# CN-Cape006-via08.net
KiCad netlist of a schematic drawn in EAGLE
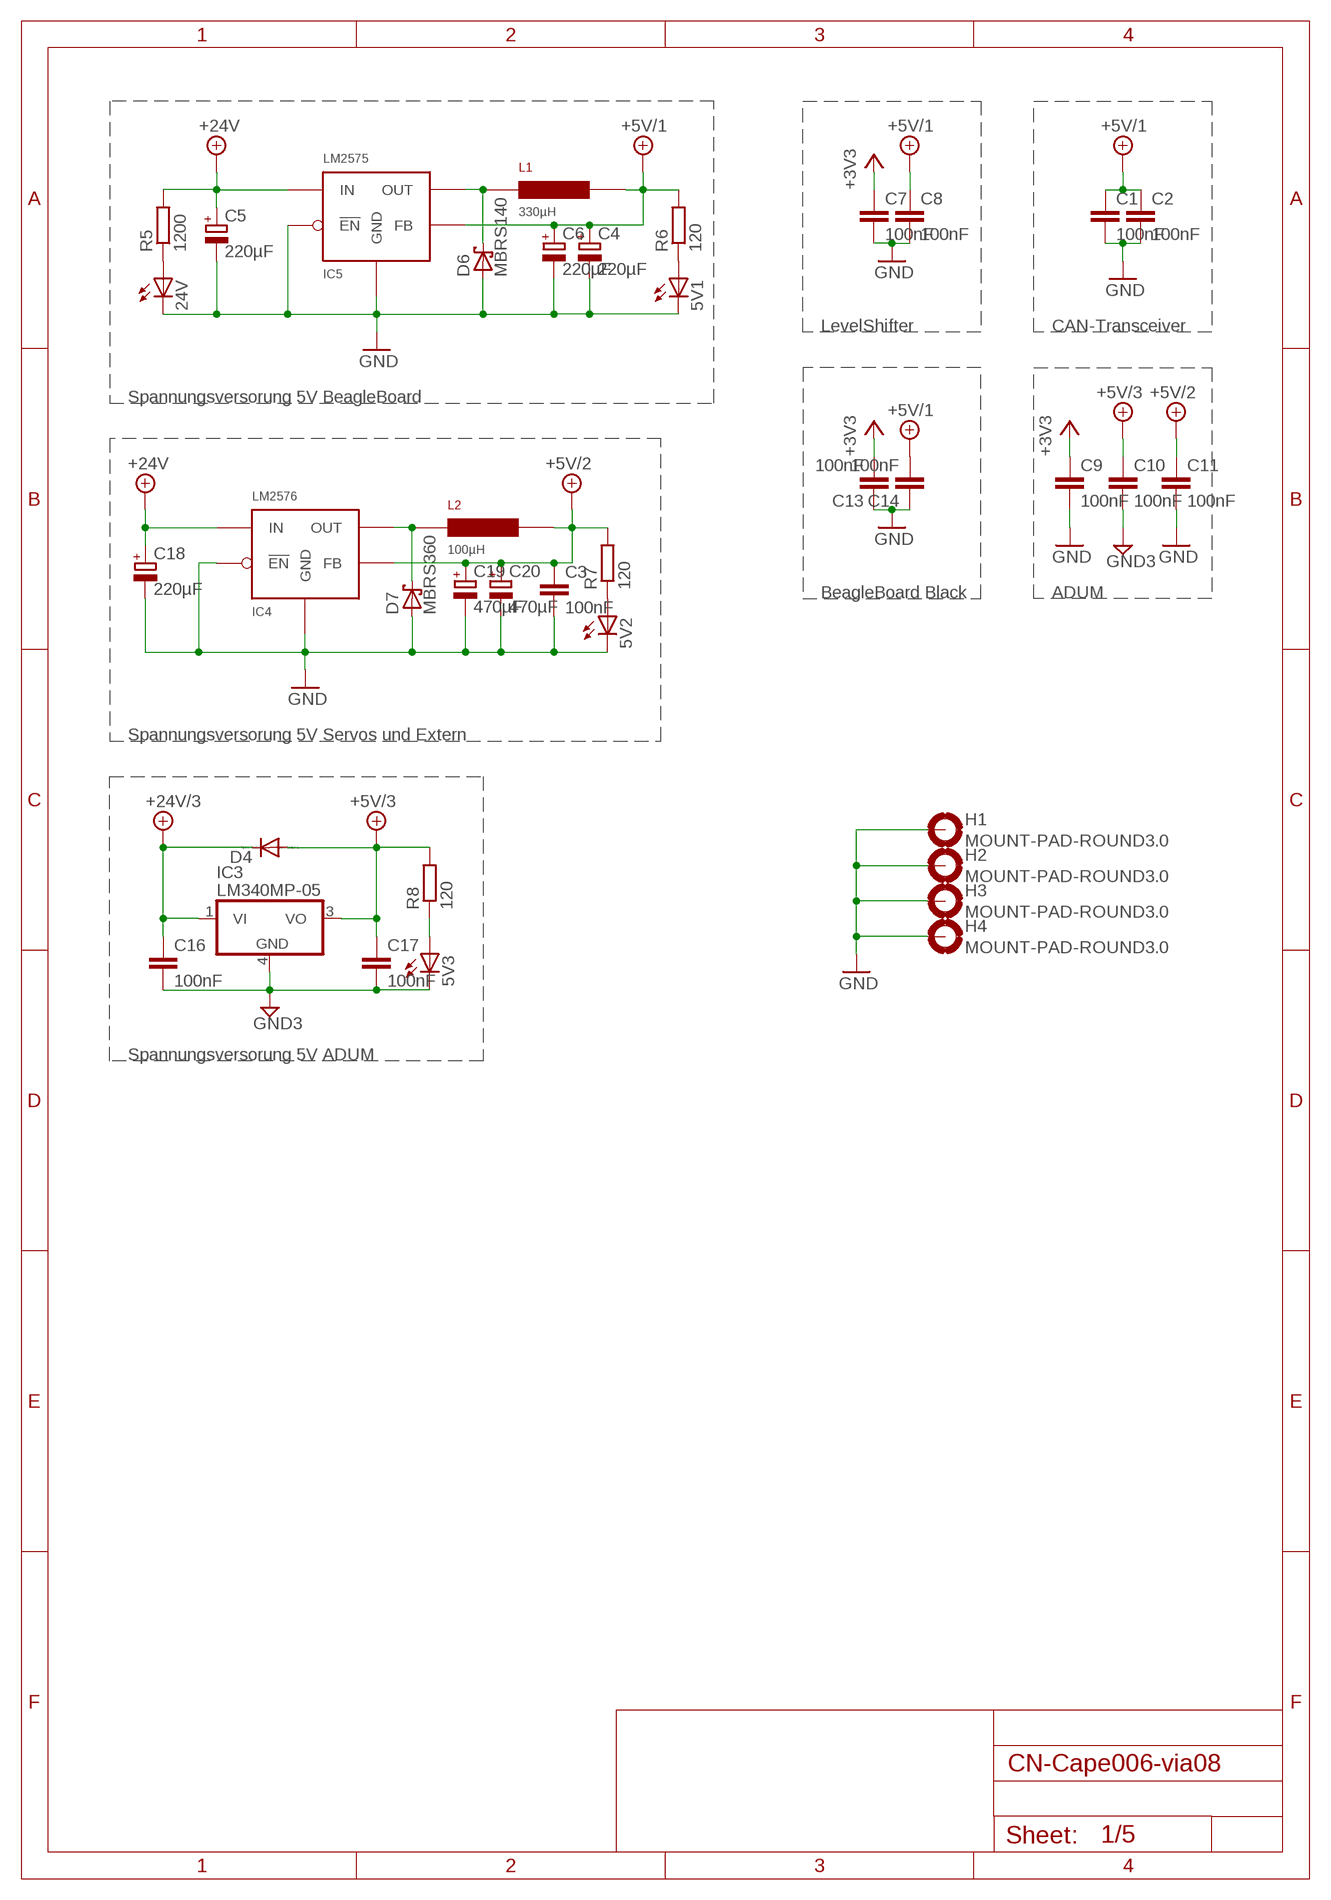
[diagram p0: schematic, sheet 1]
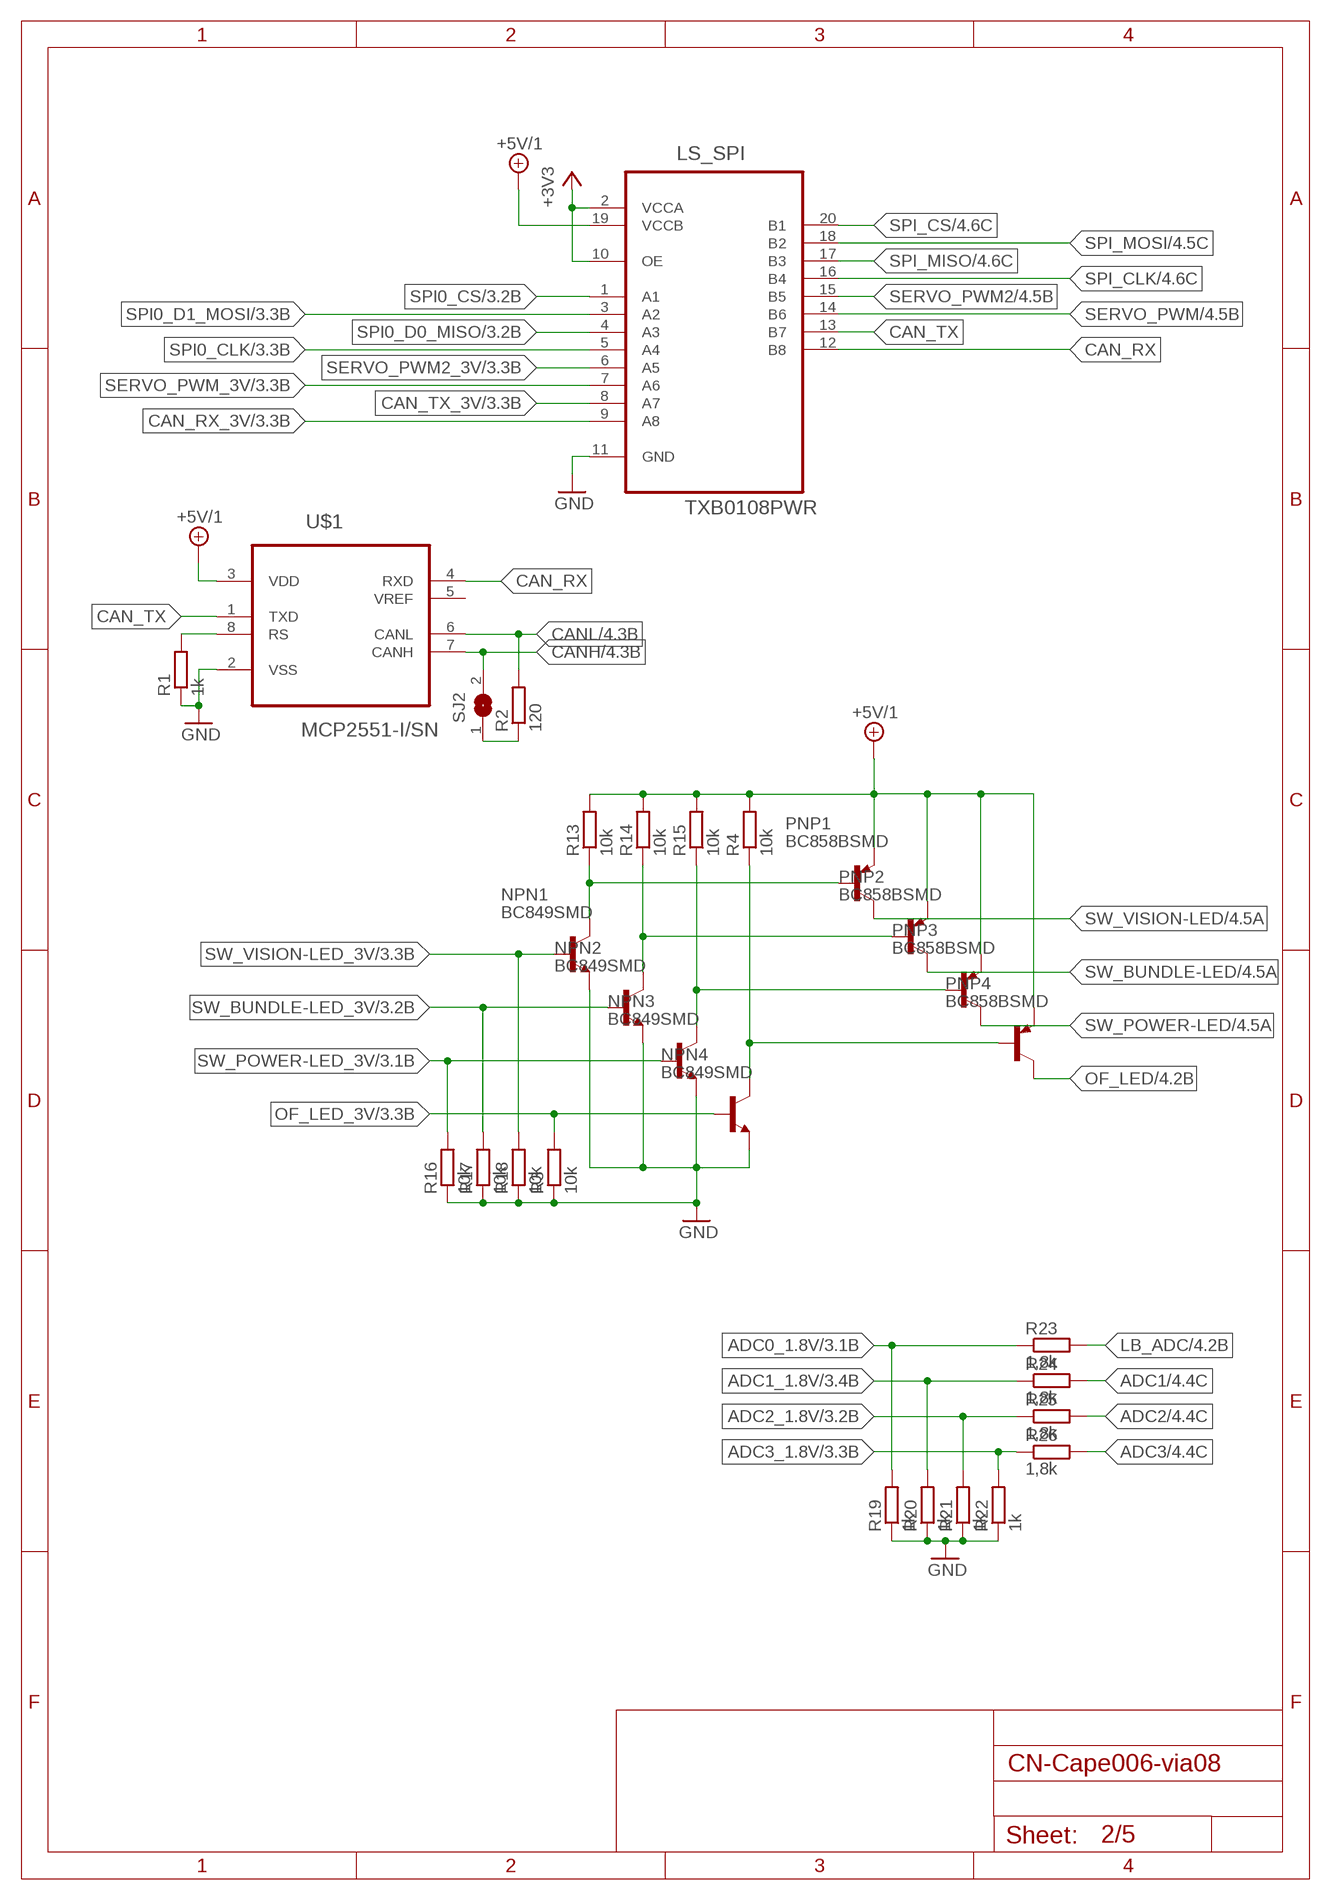
[diagram p1: schematic, sheet 2]
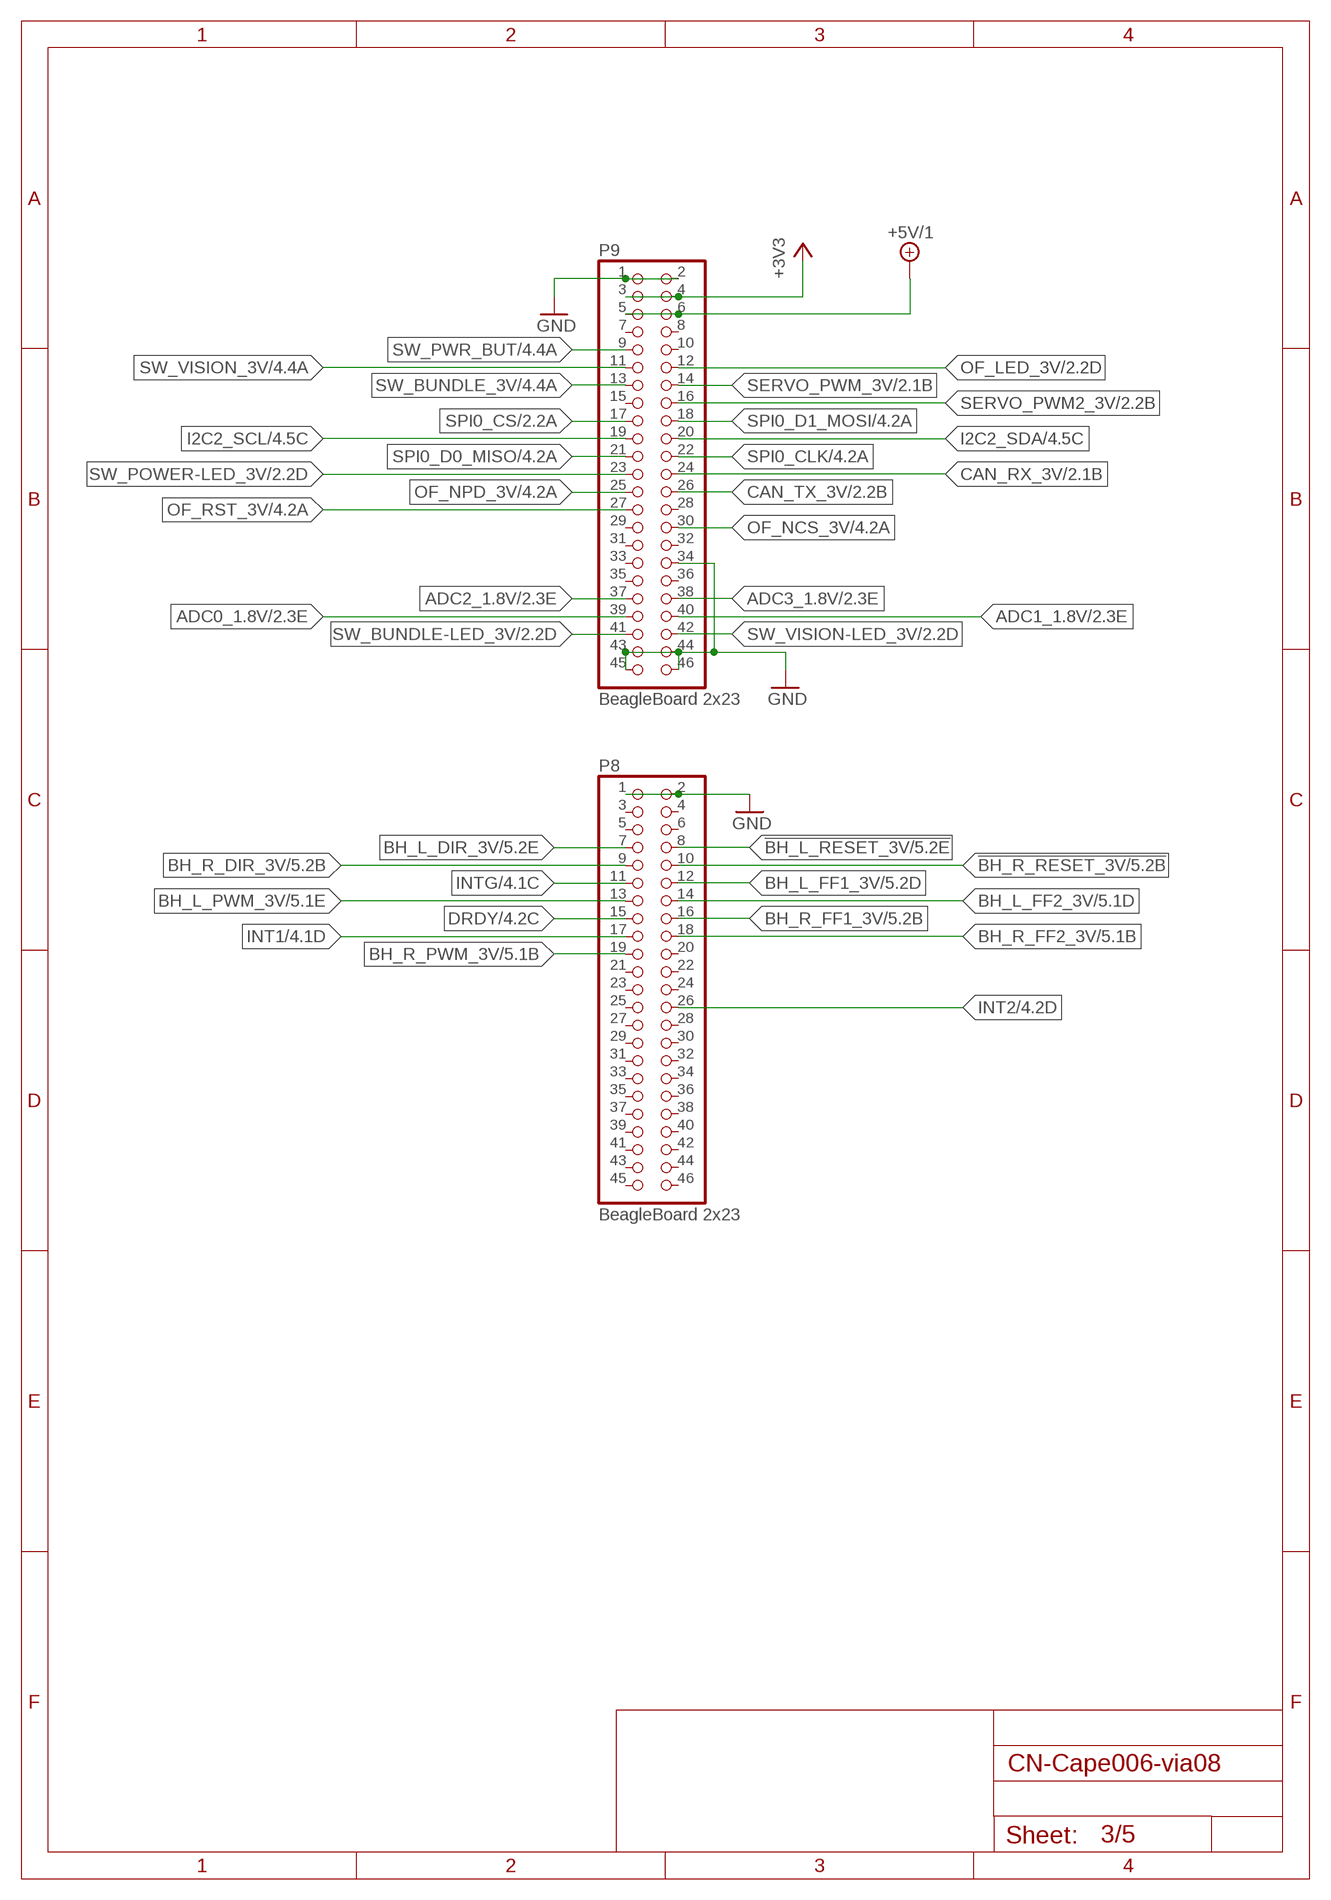
[diagram p2: schematic, sheet 3]
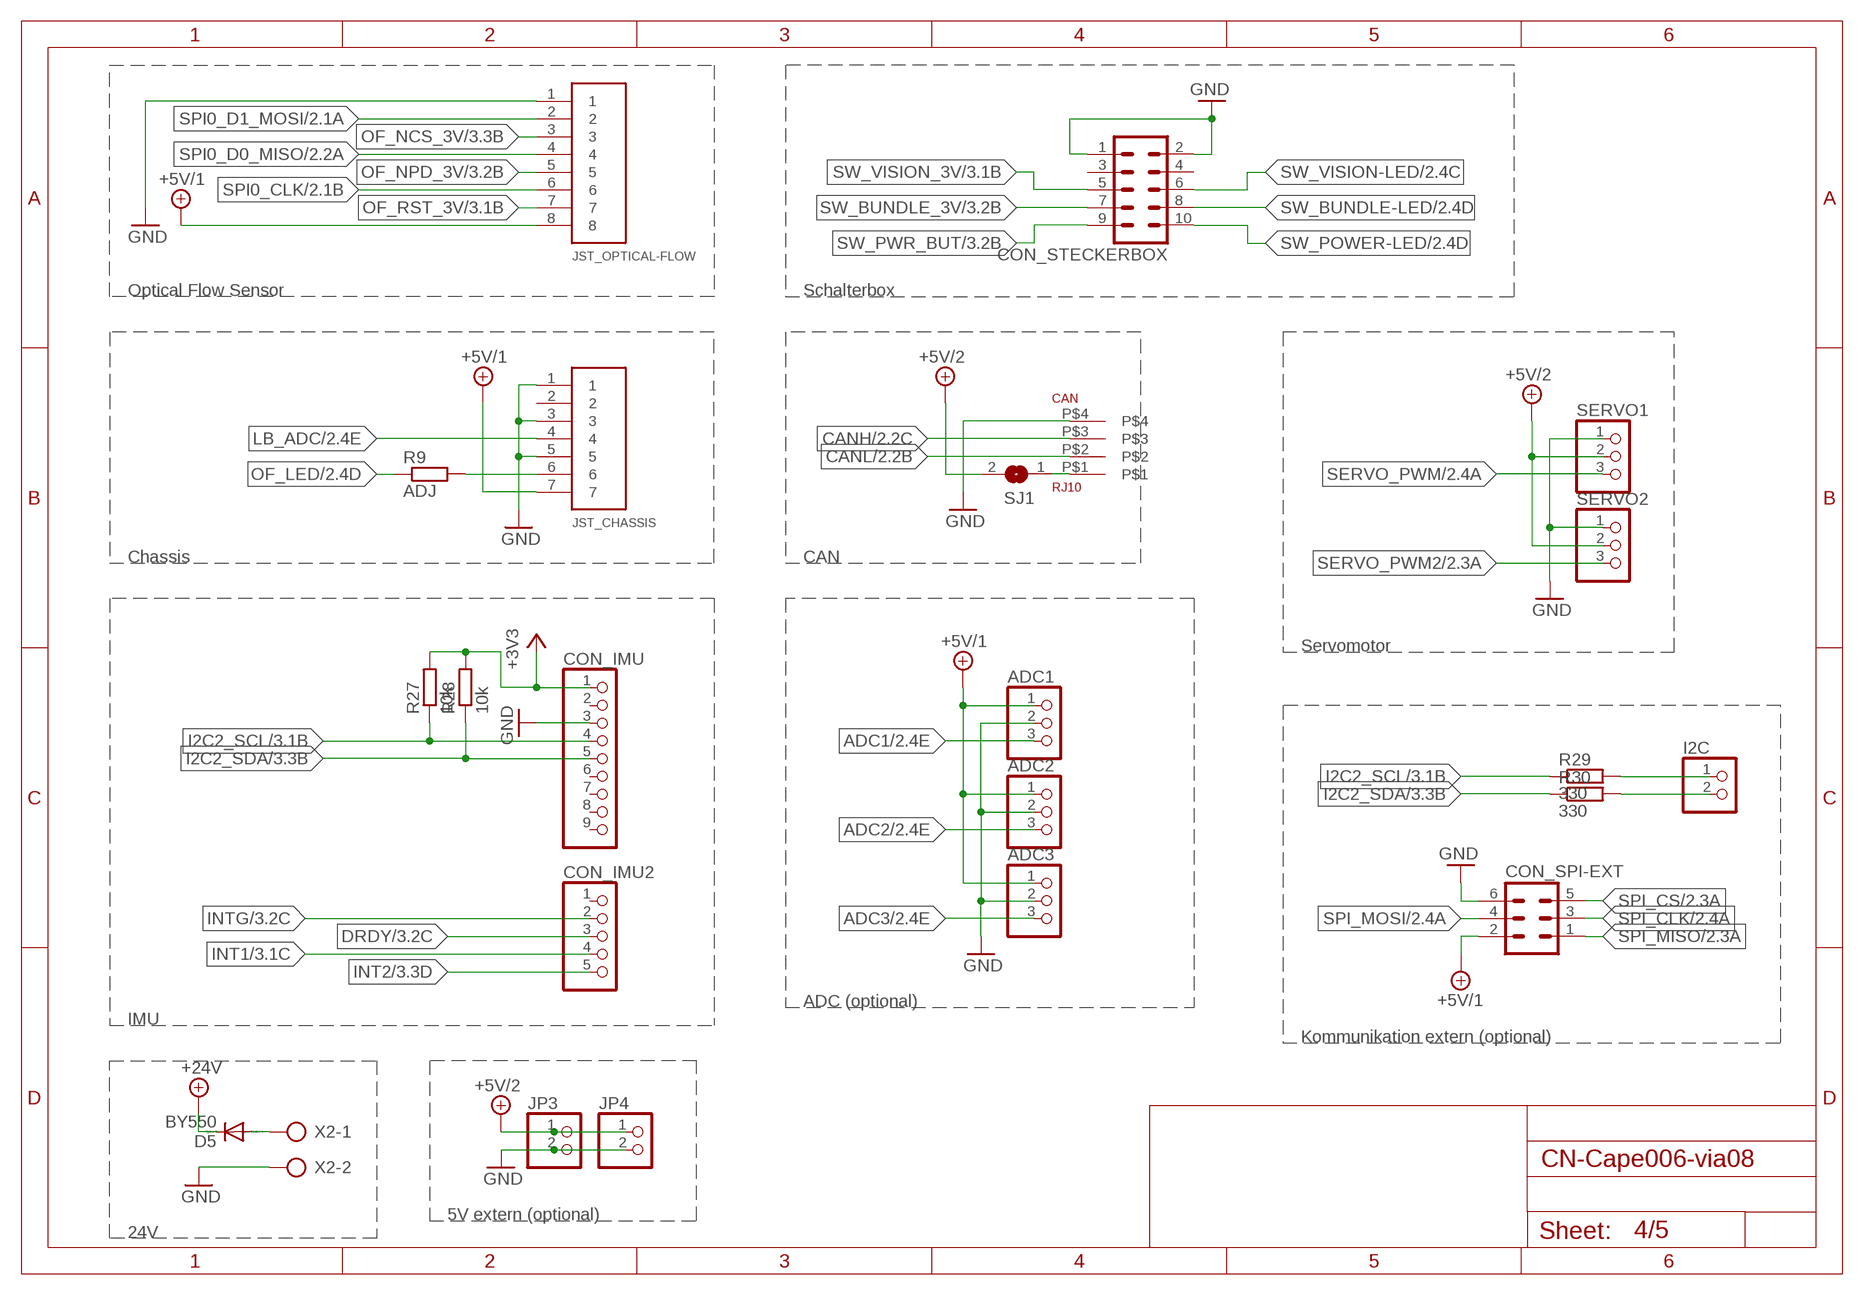
[diagram p3: schematic, sheet 4]
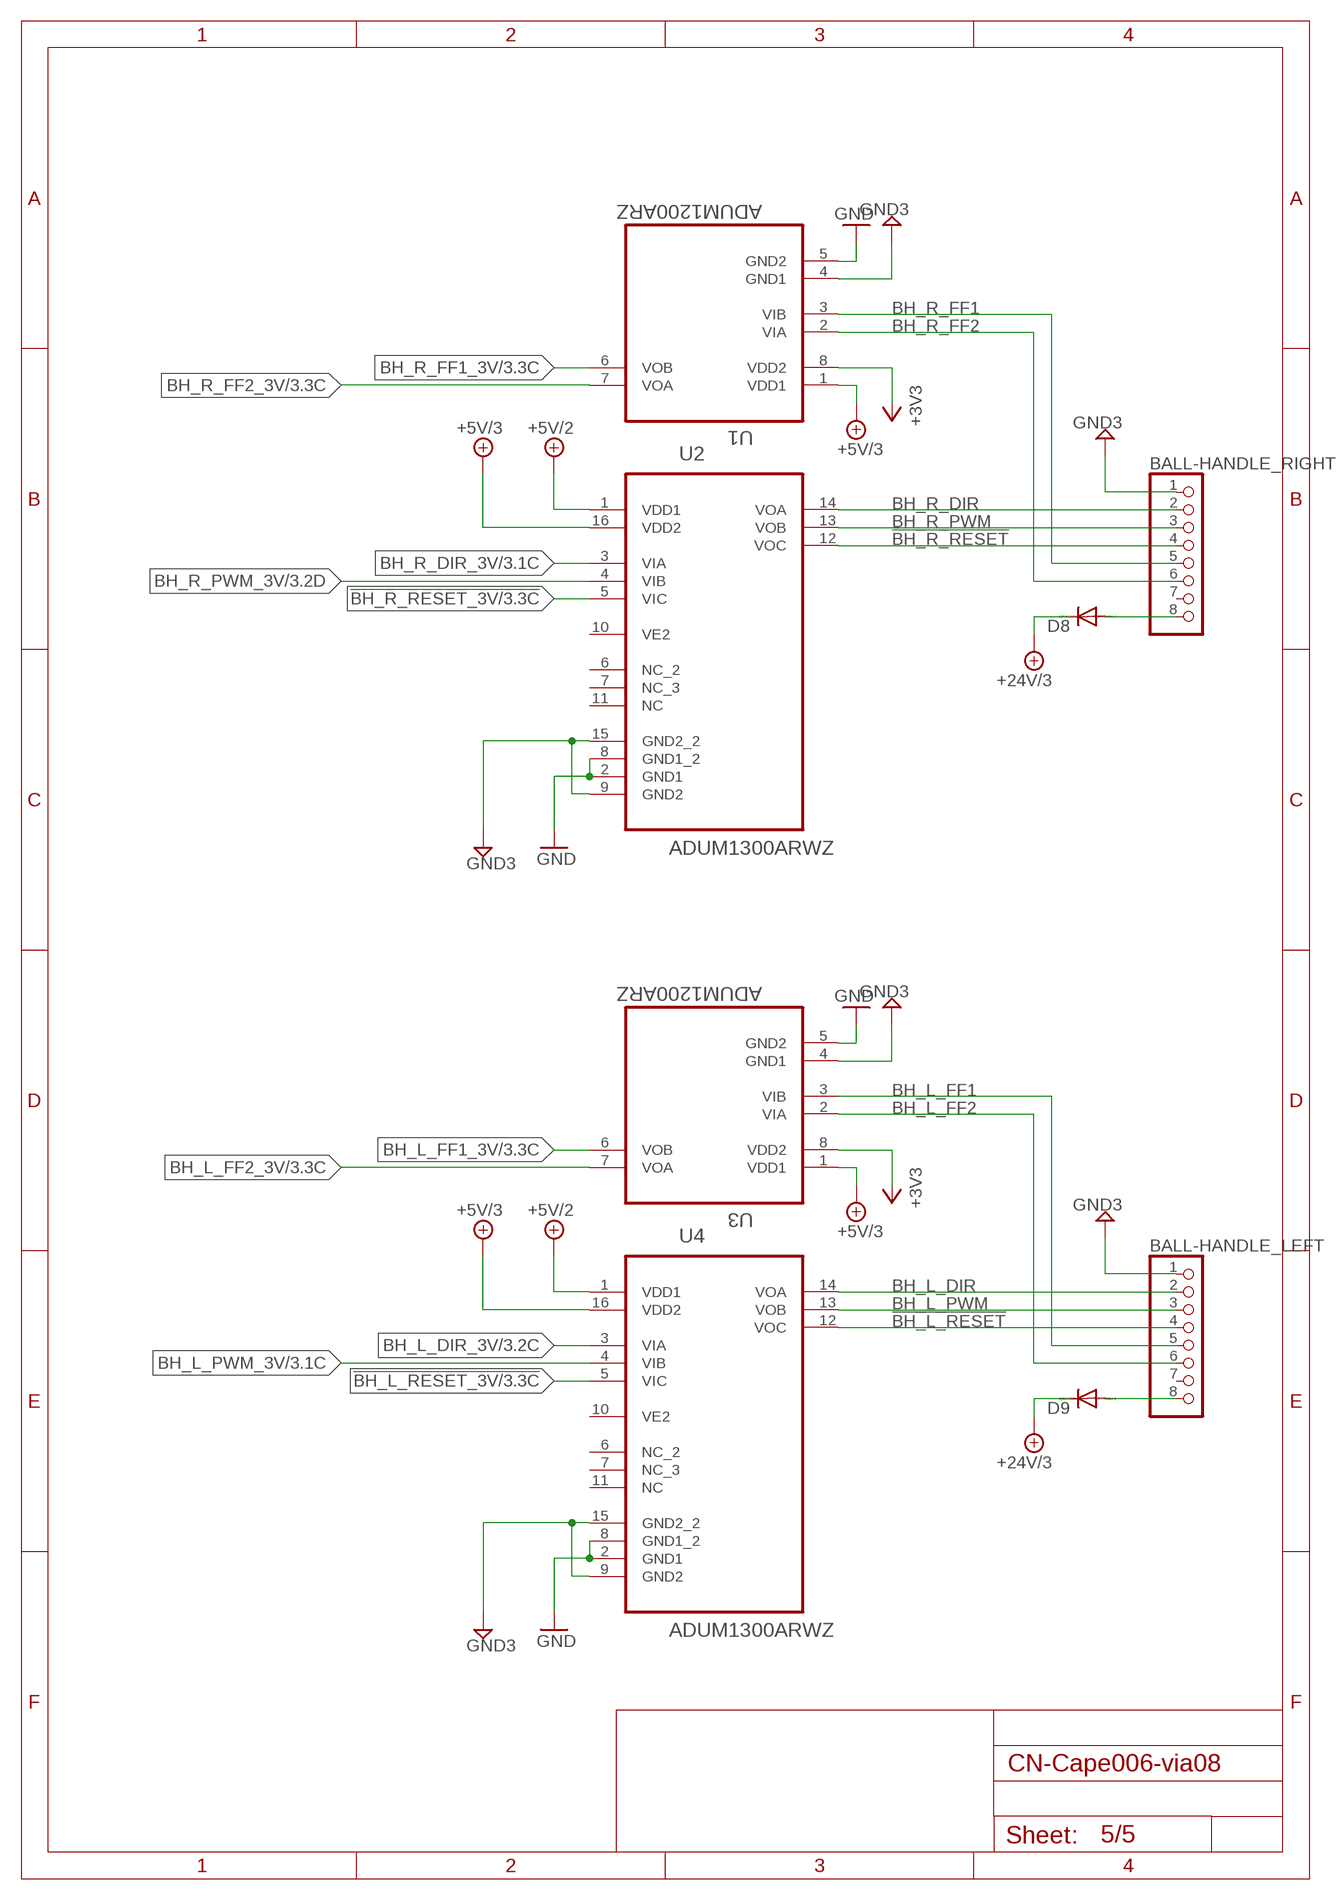
[diagram p4: schematic, sheet 5]

(export (version "E")
  (design (tool "Eeschema 10.0.6"))
  (components
    (comp (ref "5V1")
      (value "LEDCHIP-LED0603")
      (footprint "eagle-import:CHIP-LED0603")
      (libsource (lib "eagle-import") (part "LEDCHIP-LED0603"))
    )
    (comp (ref "5V2")
      (value "LEDCHIP-LED0603")
      (footprint "eagle-import:CHIP-LED0603")
      (libsource (lib "eagle-import") (part "LEDCHIP-LED0603"))
    )
    (comp (ref "5V3")
      (value "LEDCHIP-LED0603")
      (footprint "eagle-import:CHIP-LED0603")
      (libsource (lib "eagle-import") (part "LEDCHIP-LED0603"))
    )
    (comp (ref "24V")
      (value "LEDCHIP-LED0603")
      (footprint "eagle-import:CHIP-LED0603")
      (libsource (lib "eagle-import") (part "LEDCHIP-LED0603"))
    )
    (comp (ref "C1")
      (value "100nF")
      (footprint "eagle-import:C0603")
      (libsource (lib "eagle-import") (part "C-EUC0603"))
    )
    (comp (ref "C2")
      (value "100nF")
      (footprint "eagle-import:C0603")
      (libsource (lib "eagle-import") (part "C-EUC0603"))
    )
    (comp (ref "C3")
      (value "100nF")
      (footprint "eagle-import:C0603")
      (libsource (lib "eagle-import") (part "C-EUC0603"))
    )
    (comp (ref "C4")
      (value "220µF")
      (footprint "eagle-import:E2,5-6")
      (libsource (lib "eagle-import") (part "CPOL-EUE2.5-6"))
    )
    (comp (ref "C5")
      (value "220µF")
      (footprint "eagle-import:E3,5-8")
      (libsource (lib "eagle-import") (part "CPOL-EUE3.5-8"))
    )
    (comp (ref "C6")
      (value "220µF")
      (footprint "eagle-import:E2,5-6")
      (libsource (lib "eagle-import") (part "CPOL-EUE2.5-6"))
    )
    (comp (ref "C7")
      (value "100nF")
      (footprint "eagle-import:C0603")
      (libsource (lib "eagle-import") (part "C-EUC0603"))
    )
    (comp (ref "C8")
      (value "100nF")
      (footprint "eagle-import:C0603")
      (libsource (lib "eagle-import") (part "C-EUC0603"))
    )
    (comp (ref "C9")
      (value "100nF")
      (footprint "eagle-import:C0603")
      (libsource (lib "eagle-import") (part "C-EUC0603"))
    )
    (comp (ref "C10")
      (value "100nF")
      (footprint "eagle-import:C0603")
      (libsource (lib "eagle-import") (part "C-EUC0603"))
    )
    (comp (ref "C11")
      (value "100nF")
      (footprint "eagle-import:C0603")
      (libsource (lib "eagle-import") (part "C-EUC0603"))
    )
    (comp (ref "C13")
      (value "100nF")
      (footprint "eagle-import:C0603")
      (libsource (lib "eagle-import") (part "C-EUC0603"))
    )
    (comp (ref "C14")
      (value "100nF")
      (footprint "eagle-import:C0603")
      (libsource (lib "eagle-import") (part "C-EUC0603"))
    )
    (comp (ref "C16")
      (value "100nF")
      (footprint "eagle-import:C0603")
      (libsource (lib "eagle-import") (part "C-EUC0603"))
    )
    (comp (ref "C17")
      (value "100nF")
      (footprint "eagle-import:C0603")
      (libsource (lib "eagle-import") (part "C-EUC0603"))
    )
    (comp (ref "C18")
      (value "220µF")
      (footprint "eagle-import:E3,5-8")
      (libsource (lib "eagle-import") (part "CPOL-EUE3.5-8"))
    )
    (comp (ref "C19")
      (value "470µF")
      (footprint "eagle-import:E3,5-8")
      (libsource (lib "eagle-import") (part "CPOL-EUE3.5-8"))
    )
    (comp (ref "C20")
      (value "470µF")
      (footprint "eagle-import:E3,5-8")
      (libsource (lib "eagle-import") (part "CPOL-EUE3.5-8"))
    )
    (comp (ref "D4")
      (value "DIODE-SOD123")
      (footprint "eagle-import:SOD123")
      (libsource (lib "eagle-import") (part "DIODE-SOD123"))
    )
    (comp (ref "D6")
      (value "MBRS140")
      (footprint "eagle-import:SMB")
      (libsource (lib "eagle-import") (part "MBRS130LT3"))
    )
    (comp (ref "D7")
      (value "MBRS360")
      (footprint "eagle-import:SMC")
      (libsource (lib "eagle-import") (part "MBRS30T34"))
    )
    (comp (ref "H1")
      (value "MOUNT-PAD-ROUND3.0")
      (footprint "eagle-import:3,0-PAD")
      (libsource (lib "eagle-import") (part "MOUNT-PAD-ROUND3.0"))
    )
    (comp (ref "H2")
      (value "MOUNT-PAD-ROUND3.0")
      (footprint "eagle-import:3,0-PAD")
      (libsource (lib "eagle-import") (part "MOUNT-PAD-ROUND3.0"))
    )
    (comp (ref "H3")
      (value "MOUNT-PAD-ROUND3.0")
      (footprint "eagle-import:3,0-PAD")
      (libsource (lib "eagle-import") (part "MOUNT-PAD-ROUND3.0"))
    )
    (comp (ref "H4")
      (value "MOUNT-PAD-ROUND3.0")
      (footprint "eagle-import:3,0-PAD")
      (libsource (lib "eagle-import") (part "MOUNT-PAD-ROUND3.0"))
    )
    (comp (ref "IC3")
      (value "LM340MP-05")
      (footprint "eagle-import:SOT223")
      (libsource (lib "eagle-import") (part "LM340?-MP05"))
    )
    (comp (ref "IC4")
      (value "LM2576")
      (footprint "eagle-import:TO220-5_STAGGERED")
      (libsource (lib "eagle-import") (part "LM2576-T05D"))
    )
    (comp (ref "IC5")
      (value "LM2575")
      (footprint "eagle-import:TO220-5_STAGGERED")
      (libsource (lib "eagle-import") (part "LM2576-T05D"))
    )
    (comp (ref "L1")
      (value "330µH")
      (footprint "eagle-import:PISR")
      (libsource (lib "eagle-import") (part "PISR"))
    )
    (comp (ref "L2")
      (value "100µH")
      (footprint "eagle-import:PISR")
      (libsource (lib "eagle-import") (part "PISR"))
    )
    (comp (ref "R5")
      (value "1200")
      (footprint "eagle-import:R0805")
      (libsource (lib "eagle-import") (part "R-EU_R0805"))
    )
    (comp (ref "R6")
      (value "120")
      (footprint "eagle-import:R0805")
      (libsource (lib "eagle-import") (part "R-EU_R0805"))
    )
    (comp (ref "R7")
      (value "120")
      (footprint "eagle-import:R0805")
      (libsource (lib "eagle-import") (part "R-EU_R0805"))
    )
    (comp (ref "R8")
      (value "120")
      (footprint "eagle-import:R0805")
      (libsource (lib "eagle-import") (part "R-EU_R0805"))
    )
    (comp (ref "ADC1")
      (value "PINHD-1X3")
      (footprint "eagle-import:1X03")
      (libsource (lib "eagle-import") (part "PINHD-1X3"))
    )
    (comp (ref "ADC2")
      (value "PINHD-1X3")
      (footprint "eagle-import:1X03")
      (libsource (lib "eagle-import") (part "PINHD-1X3"))
    )
    (comp (ref "ADC3")
      (value "PINHD-1X3")
      (footprint "eagle-import:1X03")
      (libsource (lib "eagle-import") (part "PINHD-1X3"))
    )
    (comp (ref "CAN")
      (value "RJ10")
      (footprint "eagle-import:RJ10")
      (libsource (lib "eagle-import") (part "RJ10"))
    )
    (comp (ref "CON_IMU")
      (value "PINHD-1X9")
      (footprint "eagle-import:1X09")
      (libsource (lib "eagle-import") (part "PINHD-1X9"))
    )
    (comp (ref "CON_IMU2")
      (value "PINHD-1X5")
      (footprint "eagle-import:1X05")
      (libsource (lib "eagle-import") (part "PINHD-1X5"))
    )
    (comp (ref "CON_SPI-EXT")
      (value "ML6")
      (footprint "eagle-import:ML6")
      (libsource (lib "eagle-import") (part "ML6"))
    )
    (comp (ref "CON_STECKERBOX")
      (value "ML10")
      (footprint "eagle-import:ML10")
      (libsource (lib "eagle-import") (part "ML10"))
    )
    (comp (ref "D5")
      (value "BY550")
      (footprint "eagle-import:DO27-15")
      (libsource (lib "eagle-import") (part "BY550"))
    )
    (comp (ref "I2C")
      (value "PINHD-1X2")
      (footprint "eagle-import:1X02")
      (libsource (lib "eagle-import") (part "PINHD-1X2"))
    )
    (comp (ref "JP3")
      (value "PINHD-1X2")
      (footprint "eagle-import:1X02")
      (libsource (lib "eagle-import") (part "PINHD-1X2"))
    )
    (comp (ref "JP4")
      (value "PINHD-1X2")
      (footprint "eagle-import:1X02")
      (libsource (lib "eagle-import") (part "PINHD-1X2"))
    )
    (comp (ref "JST_CHASSIS")
      (value "S7PIN")
      (footprint "eagle-import:S7B-EH")
      (libsource (lib "eagle-import") (part "S7PIN"))
    )
    (comp (ref "JST_OPTICAL-FLOW")
      (value "S8PIN")
      (footprint "eagle-import:S8B-EH")
      (libsource (lib "eagle-import") (part "S8PIN"))
    )
    (comp (ref "R9")
      (value "ADJ")
      (footprint "eagle-import:R0805")
      (libsource (lib "eagle-import") (part "R-EU_R0805"))
    )
    (comp (ref "R27")
      (value "10k")
      (footprint "eagle-import:R0805")
      (libsource (lib "eagle-import") (part "R-EU_R0805"))
    )
    (comp (ref "R28")
      (value "10k")
      (footprint "eagle-import:R0805")
      (libsource (lib "eagle-import") (part "R-EU_R0805"))
    )
    (comp (ref "R29")
      (value "330")
      (footprint "eagle-import:R0805")
      (libsource (lib "eagle-import") (part "R-EU_R0805"))
    )
    (comp (ref "R30")
      (value "330")
      (footprint "eagle-import:R0805")
      (libsource (lib "eagle-import") (part "R-EU_R0805"))
    )
    (comp (ref "SERVO1")
      (value "PINHD-1X3")
      (footprint "eagle-import:1X03")
      (libsource (lib "eagle-import") (part "PINHD-1X3"))
    )
    (comp (ref "SERVO2")
      (value "PINHD-1X3")
      (footprint "eagle-import:1X03")
      (libsource (lib "eagle-import") (part "PINHD-1X3"))
    )
    (comp (ref "SJ1") (value "SJ") (footprint "eagle-import:SJ") (libsource (lib "eagle-import") (part "SJ")))
    (comp (ref "X2")
      (value "AK500/2-H")
      (footprint "eagle-import:AK500_2-H")
      (libsource (lib "eagle-import") (part "AK500/2-H"))
    )
    (comp (ref "LS_SPI")
      (value "TXB0108PWR")
      (footprint "eagle-import:SOP65P640X120-20N")
      (libsource (lib "eagle-import") (part "TXB0108PWR"))
    )
    (comp (ref "NPN1")
      (value "BC849SMD")
      (footprint "eagle-import:SOT23-BEC")
      (libsource (lib "eagle-import") (part "BC849SMD"))
    )
    (comp (ref "NPN2")
      (value "BC849SMD")
      (footprint "eagle-import:SOT23-BEC")
      (libsource (lib "eagle-import") (part "BC849SMD"))
    )
    (comp (ref "NPN3")
      (value "BC849SMD")
      (footprint "eagle-import:SOT23-BEC")
      (libsource (lib "eagle-import") (part "BC849SMD"))
    )
    (comp (ref "NPN4")
      (value "BC849SMD")
      (footprint "eagle-import:SOT23-BEC")
      (libsource (lib "eagle-import") (part "BC849SMD"))
    )
    (comp (ref "PNP1")
      (value "BC858BSMD")
      (footprint "eagle-import:SOT23-BEC")
      (libsource (lib "eagle-import") (part "BC858SMDB"))
    )
    (comp (ref "PNP2")
      (value "BC858BSMD")
      (footprint "eagle-import:SOT23-BEC")
      (libsource (lib "eagle-import") (part "BC858SMDB"))
    )
    (comp (ref "PNP3")
      (value "BC858BSMD")
      (footprint "eagle-import:SOT23-BEC")
      (libsource (lib "eagle-import") (part "BC858SMDB"))
    )
    (comp (ref "PNP4")
      (value "BC858BSMD")
      (footprint "eagle-import:SOT23-BEC")
      (libsource (lib "eagle-import") (part "BC858SMDB"))
    )
    (comp (ref "R1")
      (value "1k")
      (footprint "eagle-import:R0805")
      (libsource (lib "eagle-import") (part "R-EU_R0805"))
    )
    (comp (ref "R2")
      (value "120")
      (footprint "eagle-import:R0805")
      (libsource (lib "eagle-import") (part "R-EU_R0805"))
    )
    (comp (ref "R3")
      (value "10k")
      (footprint "eagle-import:R0805")
      (libsource (lib "eagle-import") (part "R-EU_R0805"))
    )
    (comp (ref "R4")
      (value "10k")
      (footprint "eagle-import:R0805")
      (libsource (lib "eagle-import") (part "R-EU_R0805"))
    )
    (comp (ref "R13")
      (value "10k")
      (footprint "eagle-import:R0805")
      (libsource (lib "eagle-import") (part "R-EU_R0805"))
    )
    (comp (ref "R14")
      (value "10k")
      (footprint "eagle-import:R0805")
      (libsource (lib "eagle-import") (part "R-EU_R0805"))
    )
    (comp (ref "R15")
      (value "10k")
      (footprint "eagle-import:R0805")
      (libsource (lib "eagle-import") (part "R-EU_R0805"))
    )
    (comp (ref "R16")
      (value "10k")
      (footprint "eagle-import:R0805")
      (libsource (lib "eagle-import") (part "R-EU_R0805"))
    )
    (comp (ref "R17")
      (value "10k")
      (footprint "eagle-import:R0805")
      (libsource (lib "eagle-import") (part "R-EU_R0805"))
    )
    (comp (ref "R18")
      (value "10k")
      (footprint "eagle-import:R0805")
      (libsource (lib "eagle-import") (part "R-EU_R0805"))
    )
    (comp (ref "R19")
      (value "1k")
      (footprint "eagle-import:R0805")
      (libsource (lib "eagle-import") (part "R-EU_R0805"))
    )
    (comp (ref "R20")
      (value "1k")
      (footprint "eagle-import:R0805")
      (libsource (lib "eagle-import") (part "R-EU_R0805"))
    )
    (comp (ref "R21")
      (value "1k")
      (footprint "eagle-import:R0805")
      (libsource (lib "eagle-import") (part "R-EU_R0805"))
    )
    (comp (ref "R22")
      (value "1k")
      (footprint "eagle-import:R0805")
      (libsource (lib "eagle-import") (part "R-EU_R0805"))
    )
    (comp (ref "R23")
      (value "1,8k")
      (footprint "eagle-import:R0805")
      (libsource (lib "eagle-import") (part "R-EU_R0805"))
    )
    (comp (ref "R24")
      (value "1,8k")
      (footprint "eagle-import:R0805")
      (libsource (lib "eagle-import") (part "R-EU_R0805"))
    )
    (comp (ref "R25")
      (value "1,8k")
      (footprint "eagle-import:R0805")
      (libsource (lib "eagle-import") (part "R-EU_R0805"))
    )
    (comp (ref "R26")
      (value "1,8k")
      (footprint "eagle-import:R0805")
      (libsource (lib "eagle-import") (part "R-EU_R0805"))
    )
    (comp (ref "SJ2") (value "SJ") (footprint "eagle-import:SJ") (libsource (lib "eagle-import") (part "SJ")))
    (comp (ref "U$1")
      (value "MCP2551-I/SN")
      (footprint "eagle-import:SOIC127P600X175-8N")
      (libsource (lib "eagle-import") (part "MCP2551-I/SN"))
    )
    (comp (ref "P8")
      (value "BeagleBoard 2x23")
      (footprint "eagle-import:2X23")
      (libsource (lib "eagle-import") (part "PINHD-2X23"))
    )
    (comp (ref "P9")
      (value "BeagleBoard 2x23")
      (footprint "eagle-import:2X23")
      (libsource (lib "eagle-import") (part "PINHD-2X23"))
    )
    (comp (ref "BALL-HANDLE_LEFT")
      (value "PINHD-1X8")
      (footprint "eagle-import:1X08")
      (libsource (lib "eagle-import") (part "PINHD-1X8"))
    )
    (comp (ref "BALL-HANDLE_RIGHT")
      (value "PINHD-1X8")
      (footprint "eagle-import:1X08")
      (libsource (lib "eagle-import") (part "PINHD-1X8"))
    )
    (comp (ref "D8")
      (value "DIODE-SOD123")
      (footprint "eagle-import:SOD123")
      (libsource (lib "eagle-import") (part "DIODE-SOD123"))
    )
    (comp (ref "D9")
      (value "DIODE-SOD123")
      (footprint "eagle-import:SOD123")
      (libsource (lib "eagle-import") (part "DIODE-SOD123"))
    )
    (comp (ref "U1")
      (value "ADUM1200ARZ")
      (footprint "eagle-import:SOIC127P600X175-8N")
      (libsource (lib "eagle-import") (part "ADUM1200ARZ"))
    )
    (comp (ref "U2")
      (value "ADUM1300ARWZ")
      (footprint "eagle-import:SOIC127P1032X265-16N")
      (libsource (lib "eagle-import") (part "ADUM1300ARWZ"))
    )
    (comp (ref "U3")
      (value "ADUM1200ARZ")
      (footprint "eagle-import:SOIC127P600X175-8N")
      (libsource (lib "eagle-import") (part "ADUM1200ARZ"))
    )
    (comp (ref "U4")
      (value "ADUM1300ARWZ")
      (footprint "eagle-import:SOIC127P1032X265-16N")
      (libsource (lib "eagle-import") (part "ADUM1300ARWZ"))
    )
  )
  (nets
    (net (code "1") (name "+3V3") (class "Default")
      (node (ref "C13") (pin "2") (pinfunction "2_2") (pintype "passive"))
      (node (ref "C7") (pin "1") (pinfunction "1_1") (pintype "passive"))
      (node (ref "C9") (pin "1") (pinfunction "1_1") (pintype "passive"))
      (node (ref "CON_IMU") (pin "1") (pinfunction "1_1") (pintype "passive"))
      (node (ref "LS_SPI") (pin "10") (pinfunction "OE_10") (pintype "input"))
      (node (ref "LS_SPI") (pin "2") (pinfunction "VCCA_2") (pintype "power_in"))
      (node (ref "P9") (pin "3") (pinfunction "3_3") (pintype "passive"))
      (node (ref "P9") (pin "4") (pinfunction "4_4") (pintype "passive"))
      (node (ref "R27") (pin "2") (pinfunction "2_2") (pintype "passive"))
      (node (ref "R28") (pin "2") (pinfunction "2_2") (pintype "passive"))
      (node (ref "U1") (pin "8") (pinfunction "VDD2_8") (pintype "power_in"))
      (node (ref "U3") (pin "8") (pinfunction "VDD2_8") (pintype "power_in"))
    )
    (net (code "2") (name "+5V{slash}1") (class "Default")
      (node (ref "ADC1") (pin "1") (pinfunction "1_1") (pintype "passive"))
      (node (ref "ADC2") (pin "1") (pinfunction "1_1") (pintype "passive"))
      (node (ref "ADC3") (pin "1") (pinfunction "1_1") (pintype "passive"))
      (node (ref "C1") (pin "1") (pinfunction "1_1") (pintype "passive"))
      (node (ref "C14") (pin "2") (pinfunction "2_2") (pintype "passive"))
      (node (ref "C2") (pin "1") (pinfunction "1_1") (pintype "passive"))
      (node (ref "C4") (pin "+") (pinfunction "+_+") (pintype "passive"))
      (node (ref "C6") (pin "+") (pinfunction "+_+") (pintype "passive"))
      (node (ref "C8") (pin "1") (pinfunction "1_1") (pintype "passive"))
      (node (ref "CON_SPI-EXT") (pin "2") (pinfunction "2_2") (pintype "passive"))
      (node (ref "IC5") (pin "FB") (pinfunction "FB_FB") (pintype "input"))
      (node (ref "JST_CHASSIS") (pin "7") (pinfunction "7_7") (pintype "bidirectional"))
      (node (ref "JST_OPTICAL-FLOW") (pin "8") (pinfunction "8_8") (pintype "bidirectional"))
      (node (ref "L1") (pin "P$2") (pinfunction "P$2_P$2") (pintype "bidirectional"))
      (node (ref "LS_SPI") (pin "19") (pinfunction "VCCB_19") (pintype "power_in"))
      (node (ref "P9") (pin "5") (pinfunction "5_5") (pintype "passive"))
      (node (ref "P9") (pin "6") (pinfunction "6_6") (pintype "passive"))
      (node (ref "PNP1") (pin "E") (pinfunction "E_E") (pintype "passive"))
      (node (ref "PNP2") (pin "E") (pinfunction "E_E") (pintype "passive"))
      (node (ref "PNP3") (pin "E") (pinfunction "E_E") (pintype "passive"))
      (node (ref "PNP4") (pin "E") (pinfunction "E_E") (pintype "passive"))
      (node (ref "R13") (pin "2") (pinfunction "2_2") (pintype "passive"))
      (node (ref "R14") (pin "2") (pinfunction "2_2") (pintype "passive"))
      (node (ref "R15") (pin "2") (pinfunction "2_2") (pintype "passive"))
      (node (ref "R4") (pin "2") (pinfunction "2_2") (pintype "passive"))
      (node (ref "R6") (pin "2") (pinfunction "2_2") (pintype "passive"))
      (node (ref "U$1") (pin "3") (pinfunction "VDD_3") (pintype "power_in"))
    )
    (net (code "3") (name "+5V{slash}2") (class "Default")
      (node (ref "C11") (pin "1") (pinfunction "1_1") (pintype "passive"))
      (node (ref "C19") (pin "+") (pinfunction "+_+") (pintype "passive"))
      (node (ref "C20") (pin "+") (pinfunction "+_+") (pintype "passive"))
      (node (ref "C3") (pin "1") (pinfunction "1_1") (pintype "passive"))
      (node (ref "IC4") (pin "FB") (pinfunction "FB_FB") (pintype "input"))
      (node (ref "JP3") (pin "1") (pinfunction "1_1") (pintype "passive"))
      (node (ref "JP4") (pin "1") (pinfunction "1_1") (pintype "passive"))
      (node (ref "L2") (pin "P$2") (pinfunction "P$2_P$2") (pintype "bidirectional"))
      (node (ref "R7") (pin "2") (pinfunction "2_2") (pintype "passive"))
      (node (ref "SERVO1") (pin "2") (pinfunction "2_2") (pintype "passive"))
      (node (ref "SERVO2") (pin "2") (pinfunction "2_2") (pintype "passive"))
      (node (ref "SJ1") (pin "2") (pinfunction "2_2") (pintype "passive"))
      (node (ref "U2") (pin "1") (pinfunction "VDD1_1") (pintype "power_in"))
      (node (ref "U4") (pin "1") (pinfunction "VDD1_1") (pintype "power_in"))
    )
    (net (code "4") (name "+5V{slash}3") (class "Default")
      (node (ref "C10") (pin "1") (pinfunction "1_1") (pintype "passive"))
      (node (ref "C17") (pin "1") (pinfunction "1_1") (pintype "passive"))
      (node (ref "D4") (pin "A") (pinfunction "A_A") (pintype "passive"))
      (node (ref "IC3") (pin "3") (pinfunction "VO_3") (pintype "passive"))
      (node (ref "R8") (pin "2") (pinfunction "2_2") (pintype "passive"))
      (node (ref "U1") (pin "1") (pinfunction "VDD1_1") (pintype "power_in"))
      (node (ref "U2") (pin "16") (pinfunction "VDD2_16") (pintype "power_in"))
      (node (ref "U3") (pin "1") (pinfunction "VDD1_1") (pintype "power_in"))
      (node (ref "U4") (pin "16") (pinfunction "VDD2_16") (pintype "power_in"))
    )
    (net (code "5") (name "+24V") (class "Default")
      (node (ref "C18") (pin "+") (pinfunction "+_+") (pintype "passive"))
      (node (ref "C5") (pin "+") (pinfunction "+_+") (pintype "passive"))
      (node (ref "D5") (pin "C") (pinfunction "C_C") (pintype "passive"))
      (node (ref "IC4") (pin "IN") (pinfunction "IN_IN") (pintype "input"))
      (node (ref "IC5") (pin "IN") (pinfunction "IN_IN") (pintype "input"))
      (node (ref "R5") (pin "2") (pinfunction "2_2") (pintype "passive"))
    )
    (net (code "6") (name "+24V{slash}3") (class "Default")
      (node (ref "C16") (pin "1") (pinfunction "1_1") (pintype "passive"))
      (node (ref "D4") (pin "C") (pinfunction "C_C") (pintype "passive"))
      (node (ref "D8") (pin "C") (pinfunction "C_C") (pintype "passive"))
      (node (ref "D9") (pin "C") (pinfunction "C_C") (pintype "passive"))
      (node (ref "IC3") (pin "1") (pinfunction "VI_1") (pintype "input"))
    )
    (net (code "7") (name "ADC0_1.8V") (class "Default")
      (node (ref "P9") (pin "39") (pinfunction "39_39") (pintype "passive"))
      (node (ref "R19") (pin "2") (pinfunction "2_2") (pintype "passive"))
      (node (ref "R23") (pin "1") (pinfunction "1_1") (pintype "passive"))
    )
    (net (code "8") (name "ADC1") (class "Default")
      (node (ref "ADC1") (pin "3") (pinfunction "3_3") (pintype "passive"))
      (node (ref "R24") (pin "2") (pinfunction "2_2") (pintype "passive"))
    )
    (net (code "9") (name "ADC1_1.8V") (class "Default")
      (node (ref "P9") (pin "40") (pinfunction "40_40") (pintype "passive"))
      (node (ref "R20") (pin "2") (pinfunction "2_2") (pintype "passive"))
      (node (ref "R24") (pin "1") (pinfunction "1_1") (pintype "passive"))
    )
    (net (code "10") (name "ADC2") (class "Default")
      (node (ref "ADC2") (pin "3") (pinfunction "3_3") (pintype "passive"))
      (node (ref "R25") (pin "2") (pinfunction "2_2") (pintype "passive"))
    )
    (net (code "11") (name "ADC2_1.8V") (class "Default")
      (node (ref "P9") (pin "37") (pinfunction "37_37") (pintype "passive"))
      (node (ref "R21") (pin "2") (pinfunction "2_2") (pintype "passive"))
      (node (ref "R25") (pin "1") (pinfunction "1_1") (pintype "passive"))
    )
    (net (code "12") (name "ADC3") (class "Default")
      (node (ref "ADC3") (pin "3") (pinfunction "3_3") (pintype "passive"))
      (node (ref "R26") (pin "2") (pinfunction "2_2") (pintype "passive"))
    )
    (net (code "13") (name "ADC3_1.8V") (class "Default")
      (node (ref "P9") (pin "38") (pinfunction "38_38") (pintype "passive"))
      (node (ref "R22") (pin "2") (pinfunction "2_2") (pintype "passive"))
      (node (ref "R26") (pin "1") (pinfunction "1_1") (pintype "passive"))
    )
    (net (code "14") (name "BH_L_DIR") (class "Default")
      (node (ref "BALL-HANDLE_LEFT") (pin "2") (pinfunction "2_2") (pintype "passive"))
      (node (ref "U4") (pin "14") (pinfunction "VOA_14") (pintype "output"))
    )
    (net (code "15") (name "BH_L_DIR_3V") (class "Default")
      (node (ref "P8") (pin "7") (pinfunction "7_7") (pintype "passive"))
      (node (ref "U4") (pin "3") (pinfunction "VIA_3") (pintype "input"))
    )
    (net (code "16") (name "BH_L_FF1") (class "Default")
      (node (ref "BALL-HANDLE_LEFT") (pin "5") (pinfunction "5_5") (pintype "passive"))
      (node (ref "U3") (pin "3") (pinfunction "VIB_3") (pintype "input"))
    )
    (net (code "17") (name "BH_L_FF1_3V") (class "Default")
      (node (ref "P8") (pin "12") (pinfunction "12_12") (pintype "passive"))
      (node (ref "U3") (pin "6") (pinfunction "VOB_6") (pintype "output"))
    )
    (net (code "18") (name "BH_L_FF2") (class "Default")
      (node (ref "BALL-HANDLE_LEFT") (pin "6") (pinfunction "6_6") (pintype "passive"))
      (node (ref "U3") (pin "2") (pinfunction "VIA_2") (pintype "input"))
    )
    (net (code "19") (name "BH_L_FF2_3V") (class "Default")
      (node (ref "P8") (pin "14") (pinfunction "14_14") (pintype "passive"))
      (node (ref "U3") (pin "7") (pinfunction "VOA_7") (pintype "output"))
    )
    (net (code "20") (name "BH_L_PWM") (class "Default")
      (node (ref "BALL-HANDLE_LEFT") (pin "3") (pinfunction "3_3") (pintype "passive"))
      (node (ref "U4") (pin "13") (pinfunction "VOB_13") (pintype "output"))
    )
    (net (code "21") (name "BH_L_PWM_3V") (class "Default")
      (node (ref "P8") (pin "13") (pinfunction "13_13") (pintype "passive"))
      (node (ref "U4") (pin "4") (pinfunction "VIB_4") (pintype "input"))
    )
    (net (code "22") (name "BH_R_DIR") (class "Default")
      (node (ref "BALL-HANDLE_RIGHT") (pin "2") (pinfunction "2_2") (pintype "passive"))
      (node (ref "U2") (pin "14") (pinfunction "VOA_14") (pintype "output"))
    )
    (net (code "23") (name "BH_R_DIR_3V") (class "Default")
      (node (ref "P8") (pin "9") (pinfunction "9_9") (pintype "passive"))
      (node (ref "U2") (pin "3") (pinfunction "VIA_3") (pintype "input"))
    )
    (net (code "24") (name "BH_R_FF1") (class "Default")
      (node (ref "BALL-HANDLE_RIGHT") (pin "5") (pinfunction "5_5") (pintype "passive"))
      (node (ref "U1") (pin "3") (pinfunction "VIB_3") (pintype "input"))
    )
    (net (code "25") (name "BH_R_FF1_3V") (class "Default")
      (node (ref "P8") (pin "16") (pinfunction "16_16") (pintype "passive"))
      (node (ref "U1") (pin "6") (pinfunction "VOB_6") (pintype "output"))
    )
    (net (code "26") (name "BH_R_FF2") (class "Default")
      (node (ref "BALL-HANDLE_RIGHT") (pin "6") (pinfunction "6_6") (pintype "passive"))
      (node (ref "U1") (pin "2") (pinfunction "VIA_2") (pintype "input"))
    )
    (net (code "27") (name "BH_R_FF2_3V") (class "Default")
      (node (ref "P8") (pin "18") (pinfunction "18_18") (pintype "passive"))
      (node (ref "U1") (pin "7") (pinfunction "VOA_7") (pintype "output"))
    )
    (net (code "28") (name "BH_R_PWM") (class "Default")
      (node (ref "BALL-HANDLE_RIGHT") (pin "3") (pinfunction "3_3") (pintype "passive"))
      (node (ref "U2") (pin "13") (pinfunction "VOB_13") (pintype "output"))
    )
    (net (code "29") (name "BH_R_PWM_3V") (class "Default")
      (node (ref "P8") (pin "19") (pinfunction "19_19") (pintype "passive"))
      (node (ref "U2") (pin "4") (pinfunction "VIB_4") (pintype "input"))
    )
    (net (code "30") (name "CANH") (class "Default")
      (node (ref "CAN") (pin "P$3") (pinfunction "P$3_P$3") (pintype "bidirectional"))
      (node (ref "SJ2") (pin "2") (pinfunction "2_2") (pintype "passive"))
      (node (ref "U$1") (pin "7") (pinfunction "CANH_7") (pintype "bidirectional"))
    )
    (net (code "31") (name "CANL") (class "Default")
      (node (ref "CAN") (pin "P$2") (pinfunction "P$2_P$2") (pintype "bidirectional"))
      (node (ref "R2") (pin "2") (pinfunction "2_2") (pintype "passive"))
      (node (ref "U$1") (pin "6") (pinfunction "CANL_6") (pintype "bidirectional"))
    )
    (net (code "32") (name "CAN_RX") (class "Default")
      (node (ref "LS_SPI") (pin "12") (pinfunction "B8_12") (pintype "bidirectional"))
      (node (ref "U$1") (pin "4") (pinfunction "RXD_4") (pintype "output"))
    )
    (net (code "33") (name "CAN_RX_3V") (class "Default")
      (node (ref "LS_SPI") (pin "9") (pinfunction "A8_9") (pintype "bidirectional"))
      (node (ref "P9") (pin "24") (pinfunction "24_24") (pintype "passive"))
    )
    (net (code "34") (name "CAN_TX") (class "Default")
      (node (ref "LS_SPI") (pin "13") (pinfunction "B7_13") (pintype "bidirectional"))
      (node (ref "U$1") (pin "1") (pinfunction "TXD_1") (pintype "input"))
    )
    (net (code "35") (name "CAN_TX_3V") (class "Default")
      (node (ref "LS_SPI") (pin "8") (pinfunction "A7_8") (pintype "bidirectional"))
      (node (ref "P9") (pin "26") (pinfunction "26_26") (pintype "passive"))
    )
    (net (code "36") (name "DRDY") (class "Default")
      (node (ref "CON_IMU2") (pin "3") (pinfunction "3_3") (pintype "passive"))
      (node (ref "P8") (pin "15") (pinfunction "15_15") (pintype "passive"))
    )
    (net (code "37") (name "GND") (class "Default")
      (node (ref "24V") (pin "C") (pinfunction "C_C") (pintype "passive"))
      (node (ref "5V1") (pin "C") (pinfunction "C_C") (pintype "passive"))
      (node (ref "5V2") (pin "C") (pinfunction "C_C") (pintype "passive"))
      (node (ref "ADC1") (pin "2") (pinfunction "2_2") (pintype "passive"))
      (node (ref "ADC2") (pin "2") (pinfunction "2_2") (pintype "passive"))
      (node (ref "ADC3") (pin "2") (pinfunction "2_2") (pintype "passive"))
      (node (ref "C1") (pin "2") (pinfunction "2_2") (pintype "passive"))
      (node (ref "C11") (pin "2") (pinfunction "2_2") (pintype "passive"))
      (node (ref "C13") (pin "1") (pinfunction "1_1") (pintype "passive"))
      (node (ref "C14") (pin "1") (pinfunction "1_1") (pintype "passive"))
      (node (ref "C18") (pin "-") (pinfunction "-_-") (pintype "passive"))
      (node (ref "C19") (pin "-") (pinfunction "-_-") (pintype "passive"))
      (node (ref "C2") (pin "2") (pinfunction "2_2") (pintype "passive"))
      (node (ref "C20") (pin "-") (pinfunction "-_-") (pintype "passive"))
      (node (ref "C3") (pin "2") (pinfunction "2_2") (pintype "passive"))
      (node (ref "C4") (pin "-") (pinfunction "-_-") (pintype "passive"))
      (node (ref "C5") (pin "-") (pinfunction "-_-") (pintype "passive"))
      (node (ref "C6") (pin "-") (pinfunction "-_-") (pintype "passive"))
      (node (ref "C7") (pin "2") (pinfunction "2_2") (pintype "passive"))
      (node (ref "C8") (pin "2") (pinfunction "2_2") (pintype "passive"))
      (node (ref "C9") (pin "2") (pinfunction "2_2") (pintype "passive"))
      (node (ref "CAN") (pin "P$4") (pinfunction "P$4_P$4") (pintype "bidirectional"))
      (node (ref "CON_IMU") (pin "3") (pinfunction "3_3") (pintype "passive"))
      (node (ref "CON_SPI-EXT") (pin "6") (pinfunction "6_6") (pintype "passive"))
      (node (ref "CON_STECKERBOX") (pin "1") (pinfunction "1_1") (pintype "passive"))
      (node (ref "CON_STECKERBOX") (pin "2") (pinfunction "2_2") (pintype "passive"))
      (node (ref "D6") (pin "A") (pinfunction "A_A") (pintype "passive"))
      (node (ref "D7") (pin "A") (pinfunction "A_A") (pintype "passive"))
      (node (ref "H1") (pin "B3,0") (pinfunction "MOUNT_B3,0") (pintype "passive"))
      (node (ref "H2") (pin "B3,0") (pinfunction "MOUNT_B3,0") (pintype "passive"))
      (node (ref "H3") (pin "B3,0") (pinfunction "MOUNT_B3,0") (pintype "passive"))
      (node (ref "H4") (pin "B3,0") (pinfunction "MOUNT_B3,0") (pintype "passive"))
      (node (ref "IC4") (pin "!EN") (pinfunction "~{EN}_!EN") (pintype "input"))
      (node (ref "IC4") (pin "GND") (pinfunction "GND_GND") (pintype "power_in"))
      (node (ref "IC5") (pin "!EN") (pinfunction "~{EN}_!EN") (pintype "input"))
      (node (ref "IC5") (pin "GND") (pinfunction "GND_GND") (pintype "power_in"))
      (node (ref "JP3") (pin "2") (pinfunction "2_2") (pintype "passive"))
      (node (ref "JP4") (pin "2") (pinfunction "2_2") (pintype "passive"))
      (node (ref "JST_CHASSIS") (pin "1") (pinfunction "1_1") (pintype "bidirectional"))
      (node (ref "JST_CHASSIS") (pin "3") (pinfunction "3_3") (pintype "bidirectional"))
      (node (ref "JST_CHASSIS") (pin "5") (pinfunction "5_5") (pintype "bidirectional"))
      (node (ref "JST_OPTICAL-FLOW") (pin "1") (pinfunction "1_1") (pintype "bidirectional"))
      (node (ref "LS_SPI") (pin "11") (pinfunction "GND_11") (pintype "passive"))
      (node (ref "NPN1") (pin "E") (pinfunction "E_E") (pintype "passive"))
      (node (ref "NPN2") (pin "E") (pinfunction "E_E") (pintype "passive"))
      (node (ref "NPN3") (pin "E") (pinfunction "E_E") (pintype "passive"))
      (node (ref "NPN4") (pin "E") (pinfunction "E_E") (pintype "passive"))
      (node (ref "P8") (pin "1") (pinfunction "1_1") (pintype "passive"))
      (node (ref "P8") (pin "2") (pinfunction "2_2") (pintype "passive"))
      (node (ref "P9") (pin "1") (pinfunction "1_1") (pintype "passive"))
      (node (ref "P9") (pin "2") (pinfunction "2_2") (pintype "passive"))
      (node (ref "P9") (pin "34") (pinfunction "34_34") (pintype "passive"))
      (node (ref "P9") (pin "43") (pinfunction "43_43") (pintype "passive"))
      (node (ref "P9") (pin "44") (pinfunction "44_44") (pintype "passive"))
      (node (ref "P9") (pin "45") (pinfunction "45_45") (pintype "passive"))
      (node (ref "P9") (pin "46") (pinfunction "46_46") (pintype "passive"))
      (node (ref "R1") (pin "1") (pinfunction "1_1") (pintype "passive"))
      (node (ref "R16") (pin "1") (pinfunction "1_1") (pintype "passive"))
      (node (ref "R17") (pin "1") (pinfunction "1_1") (pintype "passive"))
      (node (ref "R18") (pin "1") (pinfunction "1_1") (pintype "passive"))
      (node (ref "R19") (pin "1") (pinfunction "1_1") (pintype "passive"))
      (node (ref "R20") (pin "1") (pinfunction "1_1") (pintype "passive"))
      (node (ref "R21") (pin "1") (pinfunction "1_1") (pintype "passive"))
      (node (ref "R22") (pin "1") (pinfunction "1_1") (pintype "passive"))
      (node (ref "R3") (pin "1") (pinfunction "1_1") (pintype "passive"))
      (node (ref "SERVO1") (pin "1") (pinfunction "1_1") (pintype "passive"))
      (node (ref "SERVO2") (pin "1") (pinfunction "1_1") (pintype "passive"))
      (node (ref "U$1") (pin "2") (pinfunction "VSS_2") (pintype "passive"))
      (node (ref "U1") (pin "5") (pinfunction "GND2_5") (pintype "passive"))
      (node (ref "U2") (pin "2") (pinfunction "GND1_2") (pintype "passive"))
      (node (ref "U2") (pin "8") (pinfunction "GND1_2_8") (pintype "passive"))
      (node (ref "U3") (pin "5") (pinfunction "GND2_5") (pintype "passive"))
      (node (ref "U4") (pin "2") (pinfunction "GND1_2") (pintype "passive"))
      (node (ref "U4") (pin "8") (pinfunction "GND1_2_8") (pintype "passive"))
      (node (ref "X2") (pin "2") (pinfunction "KL_2") (pintype "passive"))
    )
    (net (code "38") (name "GND3") (class "Default")
      (node (ref "5V3") (pin "C") (pinfunction "C_C") (pintype "passive"))
      (node (ref "BALL-HANDLE_LEFT") (pin "1") (pinfunction "1_1") (pintype "passive"))
      (node (ref "BALL-HANDLE_RIGHT") (pin "1") (pinfunction "1_1") (pintype "passive"))
      (node (ref "C10") (pin "2") (pinfunction "2_2") (pintype "passive"))
      (node (ref "C16") (pin "2") (pinfunction "2_2") (pintype "passive"))
      (node (ref "C17") (pin "2") (pinfunction "2_2") (pintype "passive"))
      (node (ref "IC3") (pin "4") (pinfunction "GND_4") (pintype "passive"))
      (node (ref "U1") (pin "4") (pinfunction "GND1_4") (pintype "passive"))
      (node (ref "U2") (pin "15") (pinfunction "GND2_2_15") (pintype "passive"))
      (node (ref "U2") (pin "9") (pinfunction "GND2_9") (pintype "passive"))
      (node (ref "U3") (pin "4") (pinfunction "GND1_4") (pintype "passive"))
      (node (ref "U4") (pin "15") (pinfunction "GND2_2_15") (pintype "passive"))
      (node (ref "U4") (pin "9") (pinfunction "GND2_9") (pintype "passive"))
    )
    (net (code "39") (name "I2C2_SCL") (class "Default")
      (node (ref "CON_IMU") (pin "4") (pinfunction "4_4") (pintype "passive"))
      (node (ref "P9") (pin "19") (pinfunction "19_19") (pintype "passive"))
      (node (ref "R27") (pin "1") (pinfunction "1_1") (pintype "passive"))
      (node (ref "R29") (pin "1") (pinfunction "1_1") (pintype "passive"))
    )
    (net (code "40") (name "I2C2_SDA") (class "Default")
      (node (ref "CON_IMU") (pin "5") (pinfunction "5_5") (pintype "passive"))
      (node (ref "P9") (pin "20") (pinfunction "20_20") (pintype "passive"))
      (node (ref "R28") (pin "1") (pinfunction "1_1") (pintype "passive"))
      (node (ref "R30") (pin "1") (pinfunction "1_1") (pintype "passive"))
    )
    (net (code "41") (name "INT1") (class "Default")
      (node (ref "CON_IMU2") (pin "4") (pinfunction "4_4") (pintype "passive"))
      (node (ref "P8") (pin "17") (pinfunction "17_17") (pintype "passive"))
    )
    (net (code "42") (name "INT2") (class "Default")
      (node (ref "CON_IMU2") (pin "5") (pinfunction "5_5") (pintype "passive"))
      (node (ref "P8") (pin "26") (pinfunction "26_26") (pintype "passive"))
    )
    (net (code "43") (name "INTG") (class "Default")
      (node (ref "CON_IMU2") (pin "2") (pinfunction "2_2") (pintype "passive"))
      (node (ref "P8") (pin "11") (pinfunction "11_11") (pintype "passive"))
    )
    (net (code "44") (name "LB_ADC") (class "Default")
      (node (ref "JST_CHASSIS") (pin "4") (pinfunction "4_4") (pintype "bidirectional"))
      (node (ref "R23") (pin "2") (pinfunction "2_2") (pintype "passive"))
    )
    (net (code "45") (name "Net-(5V1-PadA)") (class "Default")
      (node (ref "5V1") (pin "A") (pinfunction "A_A") (pintype "passive"))
      (node (ref "R6") (pin "1") (pinfunction "1_1") (pintype "passive"))
    )
    (net (code "46") (name "Net-(5V2-PadA)") (class "Default")
      (node (ref "5V2") (pin "A") (pinfunction "A_A") (pintype "passive"))
      (node (ref "R7") (pin "1") (pinfunction "1_1") (pintype "passive"))
    )
    (net (code "47") (name "Net-(5V3-PadA)") (class "Default")
      (node (ref "5V3") (pin "A") (pinfunction "A_A") (pintype "passive"))
      (node (ref "R8") (pin "1") (pinfunction "1_1") (pintype "passive"))
    )
    (net (code "48") (name "Net-(24V-PadA)") (class "Default")
      (node (ref "24V") (pin "A") (pinfunction "A_A") (pintype "passive"))
      (node (ref "R5") (pin "1") (pinfunction "1_1") (pintype "passive"))
    )
    (net (code "49") (name "Net-(BALL-HANDLE_LEFT-Pad8)") (class "Default")
      (node (ref "BALL-HANDLE_LEFT") (pin "8") (pinfunction "8_8") (pintype "passive"))
      (node (ref "D9") (pin "A") (pinfunction "A_A") (pintype "passive"))
    )
    (net (code "50") (name "Net-(BALL-HANDLE_RIGHT-Pad8)") (class "Default")
      (node (ref "BALL-HANDLE_RIGHT") (pin "8") (pinfunction "8_8") (pintype "passive"))
      (node (ref "D8") (pin "A") (pinfunction "A_A") (pintype "passive"))
    )
    (net (code "51") (name "Net-(CAN-PadP$1)") (class "Default")
      (node (ref "CAN") (pin "P$1") (pinfunction "P$1_P$1") (pintype "bidirectional"))
      (node (ref "SJ1") (pin "1") (pinfunction "1_1") (pintype "passive"))
    )
    (net (code "52") (name "Net-(D6-PadC)") (class "Default")
      (node (ref "D6") (pin "C") (pinfunction "C_C") (pintype "passive"))
      (node (ref "IC5") (pin "OUT") (pinfunction "OUT_OUT") (pintype "output"))
      (node (ref "L1") (pin "P$1") (pinfunction "P$1_P$1") (pintype "bidirectional"))
    )
    (net (code "53") (name "Net-(D7-PadC)") (class "Default")
      (node (ref "D7") (pin "C") (pinfunction "C_C") (pintype "passive"))
      (node (ref "IC4") (pin "OUT") (pinfunction "OUT_OUT") (pintype "output"))
      (node (ref "L2") (pin "P$1") (pinfunction "P$1_P$1") (pintype "bidirectional"))
    )
    (net (code "54") (name "Net-(I2C-Pad1)") (class "Default")
      (node (ref "I2C") (pin "1") (pinfunction "1_1") (pintype "passive"))
      (node (ref "R29") (pin "2") (pinfunction "2_2") (pintype "passive"))
    )
    (net (code "55") (name "Net-(I2C-Pad2)") (class "Default")
      (node (ref "I2C") (pin "2") (pinfunction "2_2") (pintype "passive"))
      (node (ref "R30") (pin "2") (pinfunction "2_2") (pintype "passive"))
    )
    (net (code "56") (name "Net-(JST_CHASSIS-Pad6)") (class "Default")
      (node (ref "JST_CHASSIS") (pin "6") (pinfunction "6_6") (pintype "bidirectional"))
      (node (ref "R9") (pin "2") (pinfunction "2_2") (pintype "passive"))
    )
    (net (code "57") (name "Net-(NPN1-PadC)") (class "Default")
      (node (ref "NPN1") (pin "C") (pinfunction "C_C") (pintype "passive"))
      (node (ref "PNP1") (pin "B") (pinfunction "B_B") (pintype "passive"))
      (node (ref "R13") (pin "1") (pinfunction "1_1") (pintype "passive"))
    )
    (net (code "58") (name "Net-(NPN2-PadC)") (class "Default")
      (node (ref "NPN2") (pin "C") (pinfunction "C_C") (pintype "passive"))
      (node (ref "PNP2") (pin "B") (pinfunction "B_B") (pintype "passive"))
      (node (ref "R14") (pin "1") (pinfunction "1_1") (pintype "passive"))
    )
    (net (code "59") (name "Net-(NPN3-PadC)") (class "Default")
      (node (ref "NPN3") (pin "C") (pinfunction "C_C") (pintype "passive"))
      (node (ref "PNP3") (pin "B") (pinfunction "B_B") (pintype "passive"))
      (node (ref "R15") (pin "1") (pinfunction "1_1") (pintype "passive"))
    )
    (net (code "60") (name "Net-(NPN4-PadC)") (class "Default")
      (node (ref "NPN4") (pin "C") (pinfunction "C_C") (pintype "passive"))
      (node (ref "PNP4") (pin "B") (pinfunction "B_B") (pintype "passive"))
      (node (ref "R4") (pin "1") (pinfunction "1_1") (pintype "passive"))
    )
    (net (code "61") (name "Net-(R2-Pad1)") (class "Default")
      (node (ref "R2") (pin "1") (pinfunction "1_1") (pintype "passive"))
      (node (ref "SJ2") (pin "1") (pinfunction "1_1") (pintype "passive"))
    )
    (net (code "62") (name "Net-(U$1-RS)") (class "Default")
      (node (ref "R1") (pin "2") (pinfunction "2_2") (pintype "passive"))
      (node (ref "U$1") (pin "8") (pinfunction "RS_8") (pintype "input"))
    )
    (net (code "63") (name "Net-(X2A-KL)") (class "Default")
      (node (ref "D5") (pin "A") (pinfunction "A_A") (pintype "passive"))
      (node (ref "X2") (pin "1") (pinfunction "KL_1") (pintype "passive"))
    )
    (net (code "64") (name "OF_LED") (class "Default")
      (node (ref "PNP4") (pin "C") (pinfunction "C_C") (pintype "passive"))
      (node (ref "R9") (pin "1") (pinfunction "1_1") (pintype "passive"))
    )
    (net (code "65") (name "OF_LED_3V") (class "Default")
      (node (ref "NPN4") (pin "B") (pinfunction "B_B") (pintype "passive"))
      (node (ref "P9") (pin "12") (pinfunction "12_12") (pintype "passive"))
      (node (ref "R3") (pin "2") (pinfunction "2_2") (pintype "passive"))
    )
    (net (code "66") (name "OF_NCS_3V") (class "Default")
      (node (ref "JST_OPTICAL-FLOW") (pin "3") (pinfunction "3_3") (pintype "bidirectional"))
      (node (ref "P9") (pin "30") (pinfunction "30_30") (pintype "passive"))
    )
    (net (code "67") (name "OF_NPD_3V") (class "Default")
      (node (ref "JST_OPTICAL-FLOW") (pin "5") (pinfunction "5_5") (pintype "bidirectional"))
      (node (ref "P9") (pin "25") (pinfunction "25_25") (pintype "passive"))
    )
    (net (code "68") (name "OF_RST_3V") (class "Default")
      (node (ref "JST_OPTICAL-FLOW") (pin "7") (pinfunction "7_7") (pintype "bidirectional"))
      (node (ref "P9") (pin "27") (pinfunction "27_27") (pintype "passive"))
    )
    (net (code "69") (name "SERVO_PWM") (class "Default")
      (node (ref "LS_SPI") (pin "14") (pinfunction "B6_14") (pintype "bidirectional"))
      (node (ref "SERVO1") (pin "3") (pinfunction "3_3") (pintype "passive"))
    )
    (net (code "70") (name "SERVO_PWM2") (class "Default")
      (node (ref "LS_SPI") (pin "15") (pinfunction "B5_15") (pintype "bidirectional"))
      (node (ref "SERVO2") (pin "3") (pinfunction "3_3") (pintype "passive"))
    )
    (net (code "71") (name "SERVO_PWM2_3V") (class "Default")
      (node (ref "LS_SPI") (pin "6") (pinfunction "A5_6") (pintype "bidirectional"))
      (node (ref "P9") (pin "16") (pinfunction "16_16") (pintype "passive"))
    )
    (net (code "72") (name "SERVO_PWM_3V") (class "Default")
      (node (ref "LS_SPI") (pin "7") (pinfunction "A6_7") (pintype "bidirectional"))
      (node (ref "P9") (pin "14") (pinfunction "14_14") (pintype "passive"))
    )
    (net (code "73") (name "SPI0_CLK") (class "Default")
      (node (ref "JST_OPTICAL-FLOW") (pin "6") (pinfunction "6_6") (pintype "bidirectional"))
      (node (ref "LS_SPI") (pin "5") (pinfunction "A4_5") (pintype "bidirectional"))
      (node (ref "P9") (pin "22") (pinfunction "22_22") (pintype "passive"))
    )
    (net (code "74") (name "SPI0_CS") (class "Default")
      (node (ref "LS_SPI") (pin "1") (pinfunction "A1_1") (pintype "bidirectional"))
      (node (ref "P9") (pin "17") (pinfunction "17_17") (pintype "passive"))
    )
    (net (code "75") (name "SPI0_D0_MISO") (class "Default")
      (node (ref "JST_OPTICAL-FLOW") (pin "4") (pinfunction "4_4") (pintype "bidirectional"))
      (node (ref "LS_SPI") (pin "4") (pinfunction "A3_4") (pintype "bidirectional"))
      (node (ref "P9") (pin "21") (pinfunction "21_21") (pintype "passive"))
    )
    (net (code "76") (name "SPI0_D1_MOSI") (class "Default")
      (node (ref "JST_OPTICAL-FLOW") (pin "2") (pinfunction "2_2") (pintype "bidirectional"))
      (node (ref "LS_SPI") (pin "3") (pinfunction "A2_3") (pintype "bidirectional"))
      (node (ref "P9") (pin "18") (pinfunction "18_18") (pintype "passive"))
    )
    (net (code "77") (name "SPI_CLK") (class "Default")
      (node (ref "CON_SPI-EXT") (pin "3") (pinfunction "3_3") (pintype "passive"))
      (node (ref "LS_SPI") (pin "16") (pinfunction "B4_16") (pintype "bidirectional"))
    )
    (net (code "78") (name "SPI_CS") (class "Default")
      (node (ref "CON_SPI-EXT") (pin "5") (pinfunction "5_5") (pintype "passive"))
      (node (ref "LS_SPI") (pin "20") (pinfunction "B1_20") (pintype "bidirectional"))
    )
    (net (code "79") (name "SPI_MISO") (class "Default")
      (node (ref "CON_SPI-EXT") (pin "1") (pinfunction "1_1") (pintype "passive"))
      (node (ref "LS_SPI") (pin "17") (pinfunction "B3_17") (pintype "bidirectional"))
    )
    (net (code "80") (name "SPI_MOSI") (class "Default")
      (node (ref "CON_SPI-EXT") (pin "4") (pinfunction "4_4") (pintype "passive"))
      (node (ref "LS_SPI") (pin "18") (pinfunction "B2_18") (pintype "bidirectional"))
    )
    (net (code "81") (name "SW_BUNDLE-LED") (class "Default")
      (node (ref "CON_STECKERBOX") (pin "8") (pinfunction "8_8") (pintype "passive"))
      (node (ref "PNP2") (pin "C") (pinfunction "C_C") (pintype "passive"))
    )
    (net (code "82") (name "SW_BUNDLE-LED_3V") (class "Default")
      (node (ref "NPN2") (pin "B") (pinfunction "B_B") (pintype "passive"))
      (node (ref "P9") (pin "41") (pinfunction "41_41") (pintype "passive"))
      (node (ref "R17") (pin "2") (pinfunction "2_2") (pintype "passive"))
    )
    (net (code "83") (name "SW_BUNDLE_3V") (class "Default")
      (node (ref "CON_STECKERBOX") (pin "7") (pinfunction "7_7") (pintype "passive"))
      (node (ref "P9") (pin "13") (pinfunction "13_13") (pintype "passive"))
    )
    (net (code "84") (name "SW_POWER-LED") (class "Default")
      (node (ref "CON_STECKERBOX") (pin "10") (pinfunction "10_10") (pintype "passive"))
      (node (ref "PNP3") (pin "C") (pinfunction "C_C") (pintype "passive"))
    )
    (net (code "85") (name "SW_POWER-LED_3V") (class "Default")
      (node (ref "NPN3") (pin "B") (pinfunction "B_B") (pintype "passive"))
      (node (ref "P9") (pin "23") (pinfunction "23_23") (pintype "passive"))
      (node (ref "R16") (pin "2") (pinfunction "2_2") (pintype "passive"))
    )
    (net (code "86") (name "SW_PWR_BUT") (class "Default")
      (node (ref "CON_STECKERBOX") (pin "9") (pinfunction "9_9") (pintype "passive"))
      (node (ref "P9") (pin "9") (pinfunction "9_9") (pintype "passive"))
    )
    (net (code "87") (name "SW_VISION-LED") (class "Default")
      (node (ref "CON_STECKERBOX") (pin "6") (pinfunction "6_6") (pintype "passive"))
      (node (ref "PNP1") (pin "C") (pinfunction "C_C") (pintype "passive"))
    )
    (net (code "88") (name "SW_VISION-LED_3V") (class "Default")
      (node (ref "NPN1") (pin "B") (pinfunction "B_B") (pintype "passive"))
      (node (ref "P9") (pin "42") (pinfunction "42_42") (pintype "passive"))
      (node (ref "R18") (pin "2") (pinfunction "2_2") (pintype "passive"))
    )
    (net (code "89") (name "SW_VISION_3V") (class "Default")
      (node (ref "CON_STECKERBOX") (pin "5") (pinfunction "5_5") (pintype "passive"))
      (node (ref "P9") (pin "11") (pinfunction "11_11") (pintype "passive"))
    )
    (net (code "90") (name "unconnected-(BALL-HANDLE_LEFT-Pad7)") (class "Default")
      (node (ref "BALL-HANDLE_LEFT") (pin "7") (pinfunction "7_7") (pintype "passive"))
    )
    (net (code "91") (name "unconnected-(BALL-HANDLE_RIGHT-Pad7)") (class "Default")
      (node (ref "BALL-HANDLE_RIGHT") (pin "7") (pinfunction "7_7") (pintype "passive"))
    )
    (net (code "92") (name "unconnected-(CON_IMU-Pad2)") (class "Default")
      (node (ref "CON_IMU") (pin "2") (pinfunction "2_2") (pintype "passive"))
    )
    (net (code "93") (name "unconnected-(CON_IMU-Pad6)") (class "Default")
      (node (ref "CON_IMU") (pin "6") (pinfunction "6_6") (pintype "passive"))
    )
    (net (code "94") (name "unconnected-(CON_IMU-Pad7)") (class "Default")
      (node (ref "CON_IMU") (pin "7") (pinfunction "7_7") (pintype "passive"))
    )
    (net (code "95") (name "unconnected-(CON_IMU-Pad8)") (class "Default")
      (node (ref "CON_IMU") (pin "8") (pinfunction "8_8") (pintype "passive"))
    )
    (net (code "96") (name "unconnected-(CON_IMU-Pad9)") (class "Default")
      (node (ref "CON_IMU") (pin "9") (pinfunction "9_9") (pintype "passive"))
    )
    (net (code "97") (name "unconnected-(CON_IMU2-Pad1)") (class "Default")
      (node (ref "CON_IMU2") (pin "1") (pinfunction "1_1") (pintype "passive"))
    )
    (net (code "98") (name "unconnected-(CON_STECKERBOX-Pad3)") (class "Default")
      (node (ref "CON_STECKERBOX") (pin "3") (pinfunction "3_3") (pintype "passive"))
    )
    (net (code "99") (name "unconnected-(CON_STECKERBOX-Pad4)") (class "Default")
      (node (ref "CON_STECKERBOX") (pin "4") (pinfunction "4_4") (pintype "passive"))
    )
    (net (code "100") (name "unconnected-(JST_CHASSIS-Pad2)") (class "Default")
      (node (ref "JST_CHASSIS") (pin "2") (pinfunction "2_2") (pintype "bidirectional"))
    )
    (net (code "101") (name "unconnected-(P8-Pad3)") (class "Default")
      (node (ref "P8") (pin "3") (pinfunction "3_3") (pintype "passive"))
    )
    (net (code "102") (name "unconnected-(P8-Pad4)") (class "Default")
      (node (ref "P8") (pin "4") (pinfunction "4_4") (pintype "passive"))
    )
    (net (code "103") (name "unconnected-(P8-Pad5)") (class "Default")
      (node (ref "P8") (pin "5") (pinfunction "5_5") (pintype "passive"))
    )
    (net (code "104") (name "unconnected-(P8-Pad6)") (class "Default")
      (node (ref "P8") (pin "6") (pinfunction "6_6") (pintype "passive"))
    )
    (net (code "105") (name "unconnected-(P8-Pad20)") (class "Default")
      (node (ref "P8") (pin "20") (pinfunction "20_20") (pintype "passive"))
    )
    (net (code "106") (name "unconnected-(P8-Pad21)") (class "Default")
      (node (ref "P8") (pin "21") (pinfunction "21_21") (pintype "passive"))
    )
    (net (code "107") (name "unconnected-(P8-Pad22)") (class "Default")
      (node (ref "P8") (pin "22") (pinfunction "22_22") (pintype "passive"))
    )
    (net (code "108") (name "unconnected-(P8-Pad23)") (class "Default")
      (node (ref "P8") (pin "23") (pinfunction "23_23") (pintype "passive"))
    )
    (net (code "109") (name "unconnected-(P8-Pad24)") (class "Default")
      (node (ref "P8") (pin "24") (pinfunction "24_24") (pintype "passive"))
    )
    (net (code "110") (name "unconnected-(P8-Pad25)") (class "Default")
      (node (ref "P8") (pin "25") (pinfunction "25_25") (pintype "passive"))
    )
    (net (code "111") (name "unconnected-(P8-Pad27)") (class "Default")
      (node (ref "P8") (pin "27") (pinfunction "27_27") (pintype "passive"))
    )
    (net (code "112") (name "unconnected-(P8-Pad28)") (class "Default")
      (node (ref "P8") (pin "28") (pinfunction "28_28") (pintype "passive"))
    )
    (net (code "113") (name "unconnected-(P8-Pad29)") (class "Default")
      (node (ref "P8") (pin "29") (pinfunction "29_29") (pintype "passive"))
    )
    (net (code "114") (name "unconnected-(P8-Pad30)") (class "Default")
      (node (ref "P8") (pin "30") (pinfunction "30_30") (pintype "passive"))
    )
    (net (code "115") (name "unconnected-(P8-Pad31)") (class "Default")
      (node (ref "P8") (pin "31") (pinfunction "31_31") (pintype "passive"))
    )
    (net (code "116") (name "unconnected-(P8-Pad32)") (class "Default")
      (node (ref "P8") (pin "32") (pinfunction "32_32") (pintype "passive"))
    )
    (net (code "117") (name "unconnected-(P8-Pad33)") (class "Default")
      (node (ref "P8") (pin "33") (pinfunction "33_33") (pintype "passive"))
    )
    (net (code "118") (name "unconnected-(P8-Pad34)") (class "Default")
      (node (ref "P8") (pin "34") (pinfunction "34_34") (pintype "passive"))
    )
    (net (code "119") (name "unconnected-(P8-Pad35)") (class "Default")
      (node (ref "P8") (pin "35") (pinfunction "35_35") (pintype "passive"))
    )
    (net (code "120") (name "unconnected-(P8-Pad36)") (class "Default")
      (node (ref "P8") (pin "36") (pinfunction "36_36") (pintype "passive"))
    )
    (net (code "121") (name "unconnected-(P8-Pad37)") (class "Default")
      (node (ref "P8") (pin "37") (pinfunction "37_37") (pintype "passive"))
    )
    (net (code "122") (name "unconnected-(P8-Pad38)") (class "Default")
      (node (ref "P8") (pin "38") (pinfunction "38_38") (pintype "passive"))
    )
    (net (code "123") (name "unconnected-(P8-Pad39)") (class "Default")
      (node (ref "P8") (pin "39") (pinfunction "39_39") (pintype "passive"))
    )
    (net (code "124") (name "unconnected-(P8-Pad40)") (class "Default")
      (node (ref "P8") (pin "40") (pinfunction "40_40") (pintype "passive"))
    )
    (net (code "125") (name "unconnected-(P8-Pad41)") (class "Default")
      (node (ref "P8") (pin "41") (pinfunction "41_41") (pintype "passive"))
    )
    (net (code "126") (name "unconnected-(P8-Pad42)") (class "Default")
      (node (ref "P8") (pin "42") (pinfunction "42_42") (pintype "passive"))
    )
    (net (code "127") (name "unconnected-(P8-Pad43)") (class "Default")
      (node (ref "P8") (pin "43") (pinfunction "43_43") (pintype "passive"))
    )
    (net (code "128") (name "unconnected-(P8-Pad44)") (class "Default")
      (node (ref "P8") (pin "44") (pinfunction "44_44") (pintype "passive"))
    )
    (net (code "129") (name "unconnected-(P8-Pad45)") (class "Default")
      (node (ref "P8") (pin "45") (pinfunction "45_45") (pintype "passive"))
    )
    (net (code "130") (name "unconnected-(P8-Pad46)") (class "Default")
      (node (ref "P8") (pin "46") (pinfunction "46_46") (pintype "passive"))
    )
    (net (code "131") (name "unconnected-(P9-Pad7)") (class "Default")
      (node (ref "P9") (pin "7") (pinfunction "7_7") (pintype "passive"))
    )
    (net (code "132") (name "unconnected-(P9-Pad8)") (class "Default")
      (node (ref "P9") (pin "8") (pinfunction "8_8") (pintype "passive"))
    )
    (net (code "133") (name "unconnected-(P9-Pad10)") (class "Default")
      (node (ref "P9") (pin "10") (pinfunction "10_10") (pintype "passive"))
    )
    (net (code "134") (name "unconnected-(P9-Pad15)") (class "Default")
      (node (ref "P9") (pin "15") (pinfunction "15_15") (pintype "passive"))
    )
    (net (code "135") (name "unconnected-(P9-Pad28)") (class "Default")
      (node (ref "P9") (pin "28") (pinfunction "28_28") (pintype "passive"))
    )
    (net (code "136") (name "unconnected-(P9-Pad29)") (class "Default")
      (node (ref "P9") (pin "29") (pinfunction "29_29") (pintype "passive"))
    )
    (net (code "137") (name "unconnected-(P9-Pad31)") (class "Default")
      (node (ref "P9") (pin "31") (pinfunction "31_31") (pintype "passive"))
    )
    (net (code "138") (name "unconnected-(P9-Pad32)") (class "Default")
      (node (ref "P9") (pin "32") (pinfunction "32_32") (pintype "passive"))
    )
    (net (code "139") (name "unconnected-(P9-Pad33)") (class "Default")
      (node (ref "P9") (pin "33") (pinfunction "33_33") (pintype "passive"))
    )
    (net (code "140") (name "unconnected-(P9-Pad35)") (class "Default")
      (node (ref "P9") (pin "35") (pinfunction "35_35") (pintype "passive"))
    )
    (net (code "141") (name "unconnected-(P9-Pad36)") (class "Default")
      (node (ref "P9") (pin "36") (pinfunction "36_36") (pintype "passive"))
    )
    (net (code "142") (name "unconnected-(U$1-VREF-Pad5)") (class "Default")
      (node (ref "U$1") (pin "5") (pinfunction "VREF_5") (pintype "output"))
    )
    (net (code "143") (name "unconnected-(U2-NC-Pad11)") (class "Default")
      (node (ref "U2") (pin "11") (pinfunction "NC_11") (pintype "no_connect"))
    )
    (net (code "144") (name "unconnected-(U2-NC_2-Pad6)") (class "Default")
      (node (ref "U2") (pin "6") (pinfunction "NC_2_6") (pintype "no_connect"))
    )
    (net (code "145") (name "unconnected-(U2-NC_3-Pad7)") (class "Default")
      (node (ref "U2") (pin "7") (pinfunction "NC_3_7") (pintype "no_connect"))
    )
    (net (code "146") (name "unconnected-(U2-VE2-Pad10)") (class "Default")
      (node (ref "U2") (pin "10") (pinfunction "VE2_10") (pintype "input"))
    )
    (net (code "147") (name "unconnected-(U4-NC-Pad11)") (class "Default")
      (node (ref "U4") (pin "11") (pinfunction "NC_11") (pintype "no_connect"))
    )
    (net (code "148") (name "unconnected-(U4-NC_2-Pad6)") (class "Default")
      (node (ref "U4") (pin "6") (pinfunction "NC_2_6") (pintype "no_connect"))
    )
    (net (code "149") (name "unconnected-(U4-NC_3-Pad7)") (class "Default")
      (node (ref "U4") (pin "7") (pinfunction "NC_3_7") (pintype "no_connect"))
    )
    (net (code "150") (name "unconnected-(U4-VE2-Pad10)") (class "Default")
      (node (ref "U4") (pin "10") (pinfunction "VE2_10") (pintype "input"))
    )
    (net (code "151") (name "~{BH_L_RESET_3V}") (class "Default")
      (node (ref "P8") (pin "8") (pinfunction "8_8") (pintype "passive"))
      (node (ref "U4") (pin "5") (pinfunction "VIC_5") (pintype "input"))
    )
    (net (code "152") (name "~{BH_L_RESET}") (class "Default")
      (node (ref "BALL-HANDLE_LEFT") (pin "4") (pinfunction "4_4") (pintype "passive"))
      (node (ref "U4") (pin "12") (pinfunction "VOC_12") (pintype "output"))
    )
    (net (code "153") (name "~{BH_R_RESET_3V}") (class "Default")
      (node (ref "P8") (pin "10") (pinfunction "10_10") (pintype "passive"))
      (node (ref "U2") (pin "5") (pinfunction "VIC_5") (pintype "input"))
    )
    (net (code "154") (name "~{BH_R_RESET}") (class "Default")
      (node (ref "BALL-HANDLE_RIGHT") (pin "4") (pinfunction "4_4") (pintype "passive"))
      (node (ref "U2") (pin "12") (pinfunction "VOC_12") (pintype "output"))
    )
  )
)
